# Arm_Board_2018.net
KiCad netlist of a schematic drawn in EAGLE
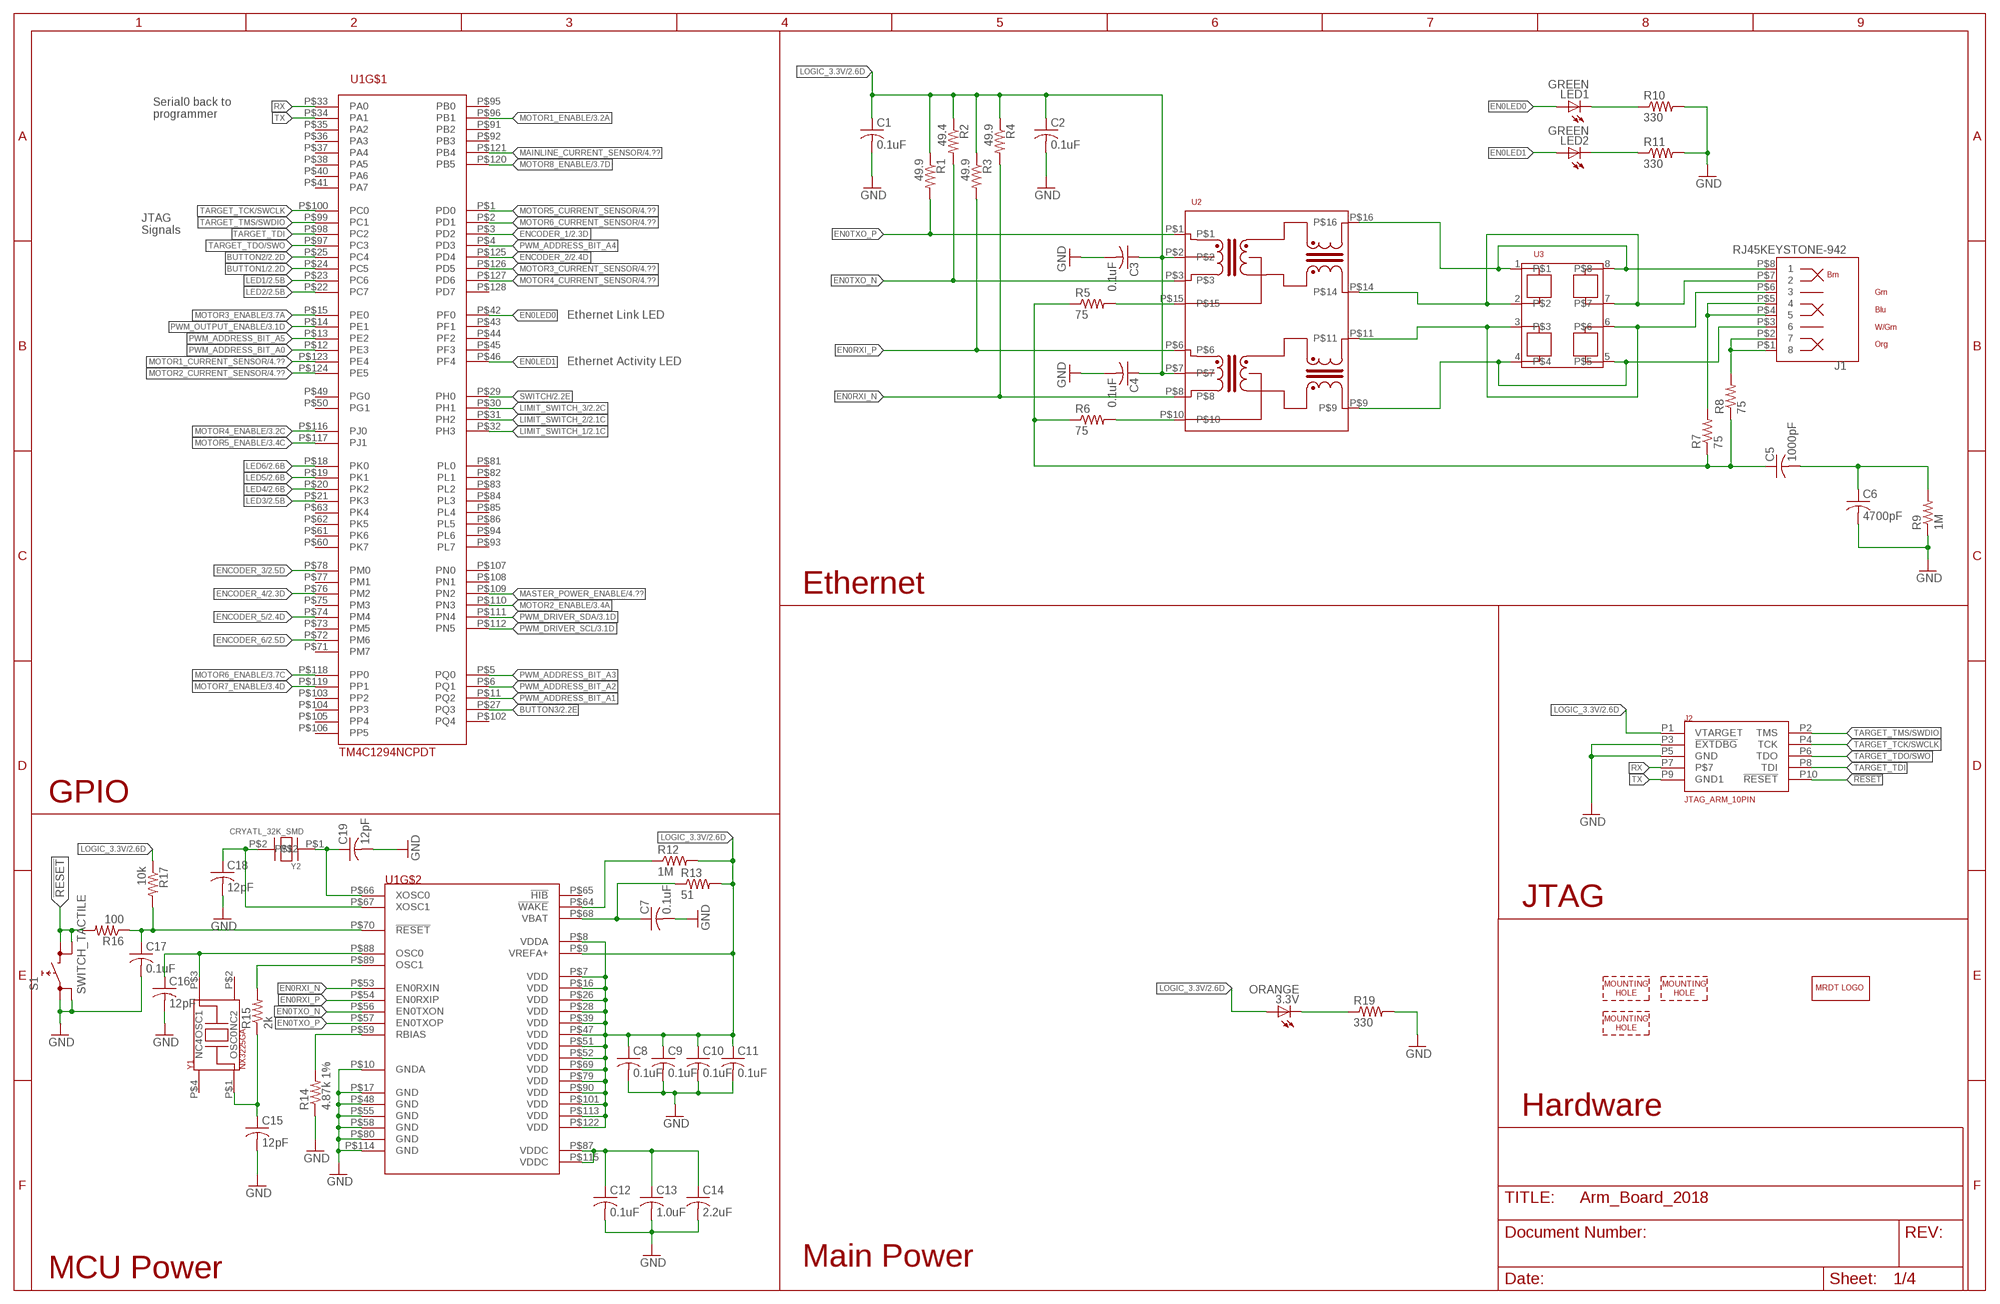
[diagram p0: schematic, sheet 1]
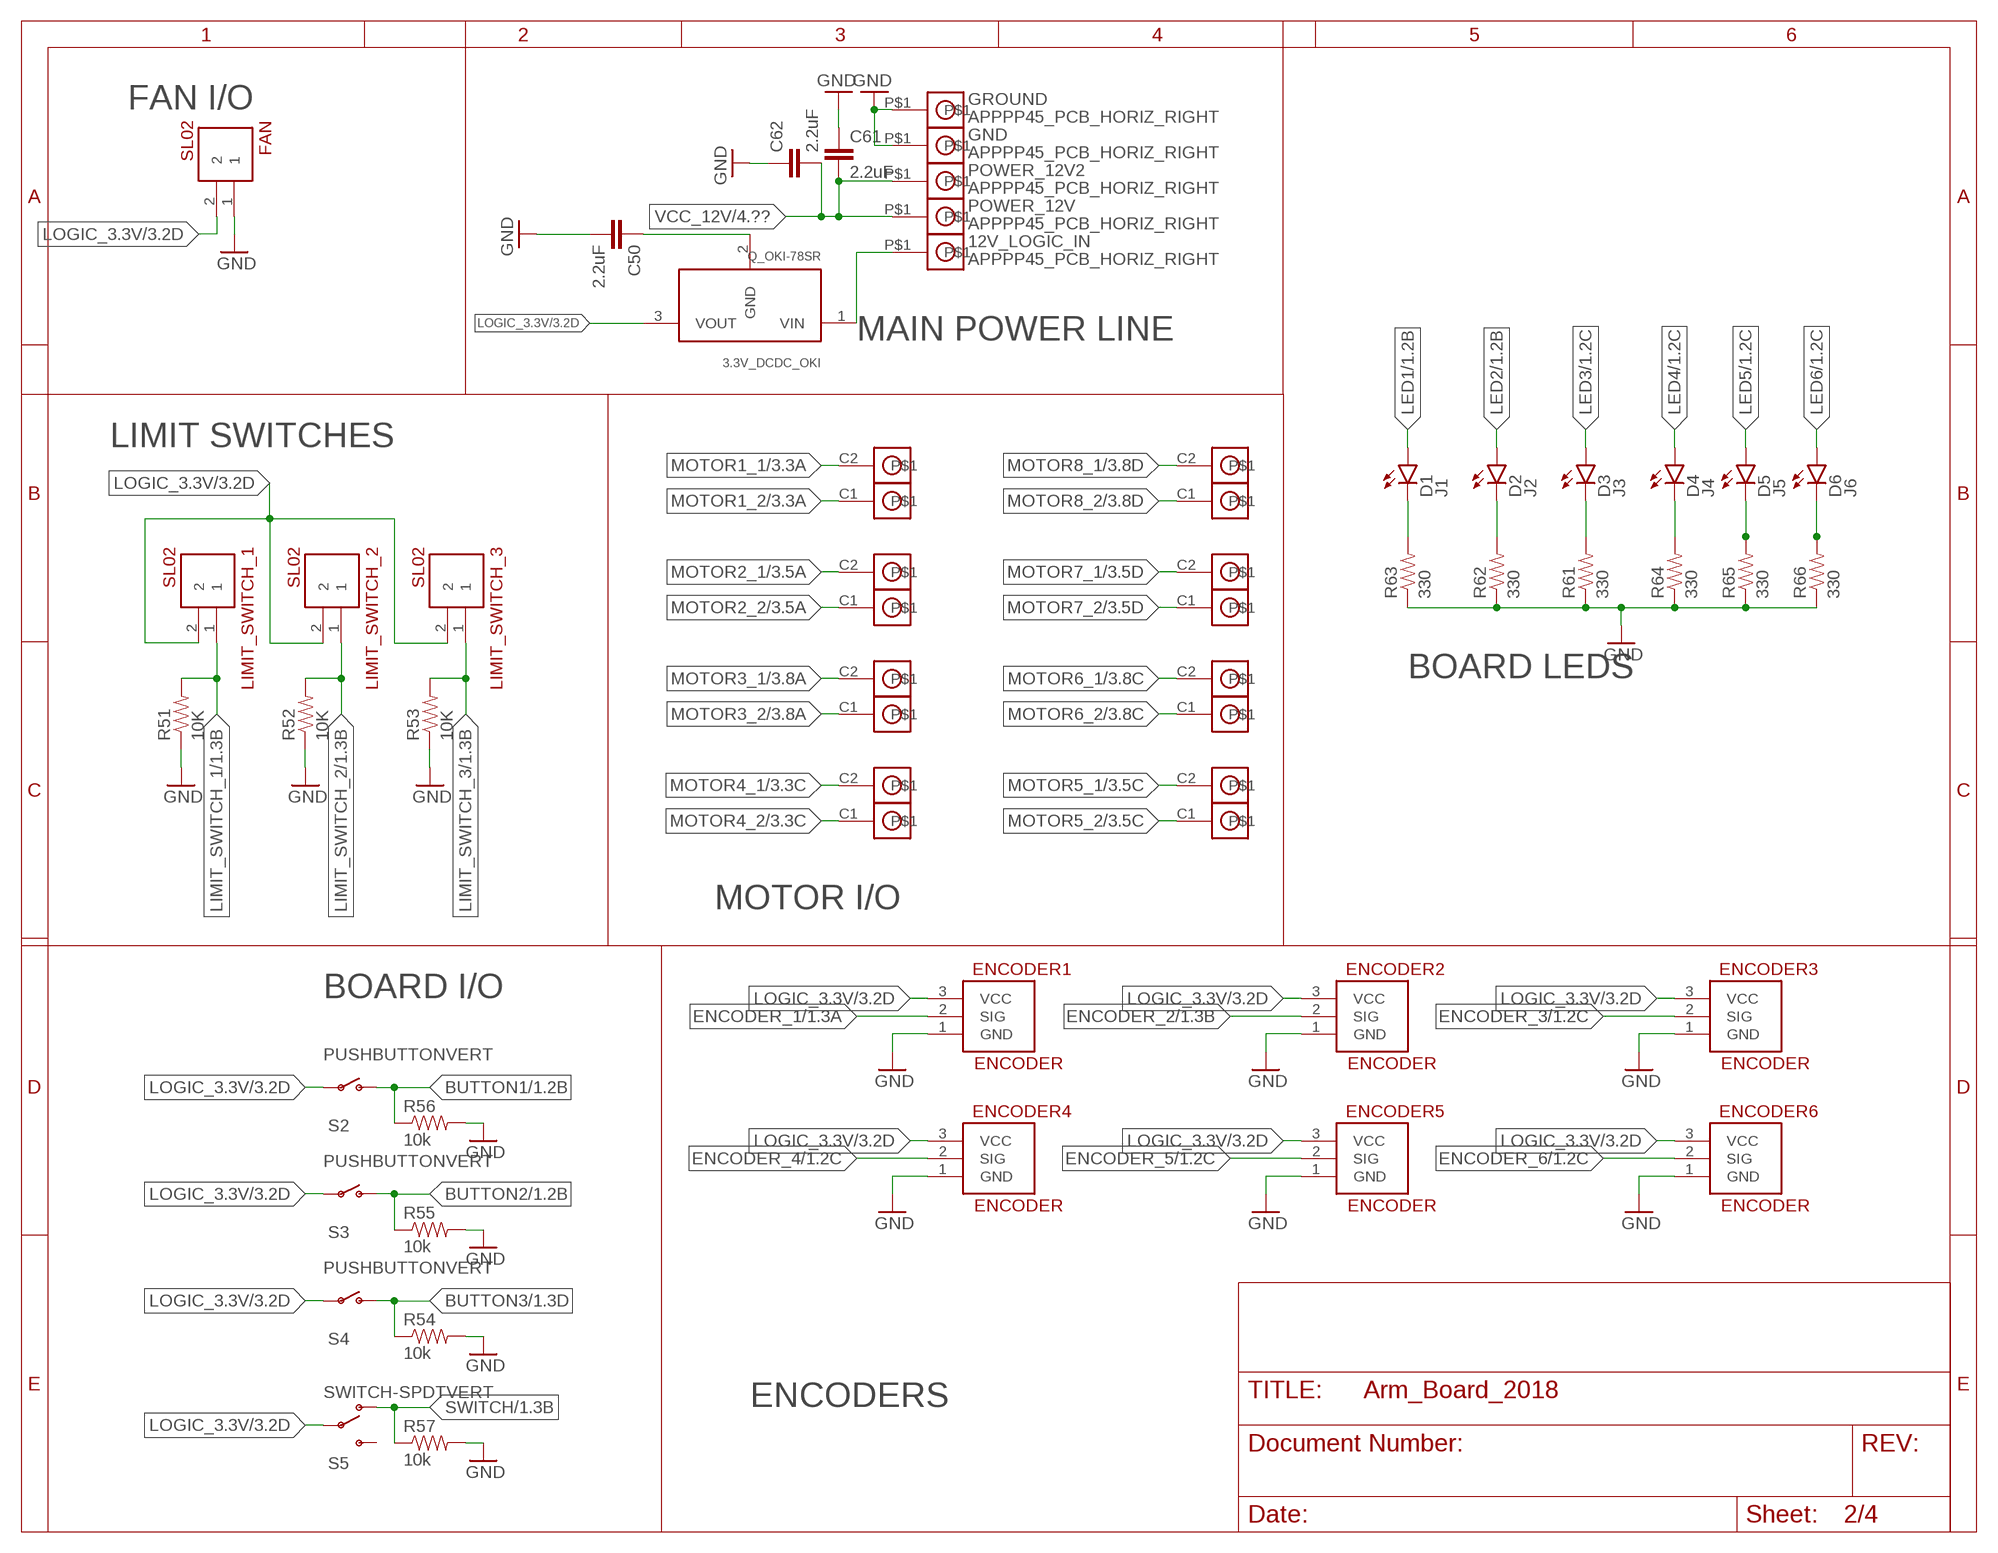
[diagram p1: schematic, sheet 2]
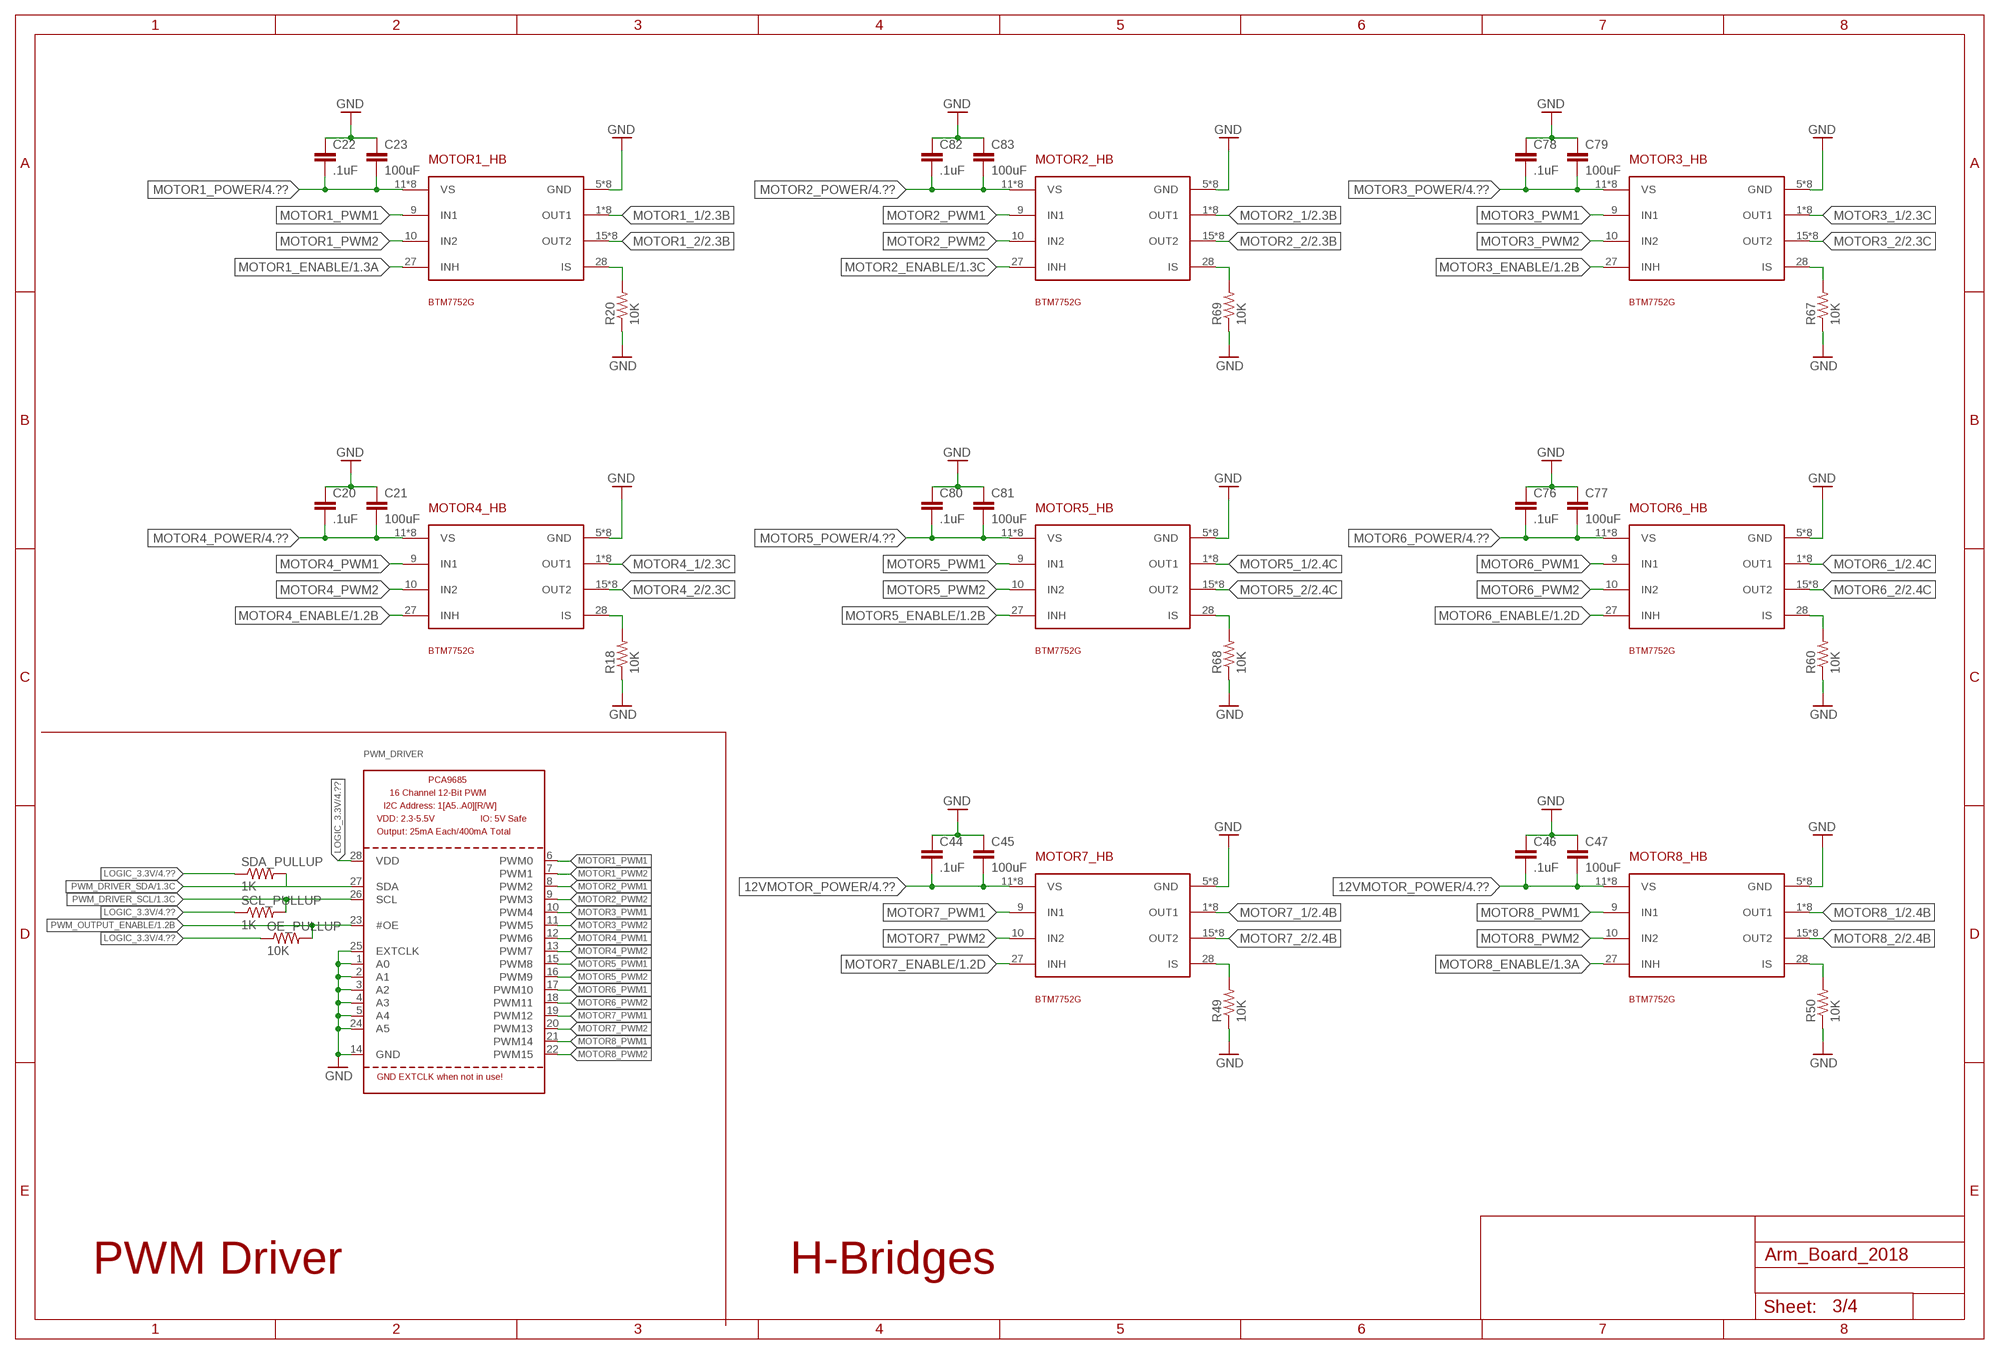
[diagram p2: schematic, sheet 3]
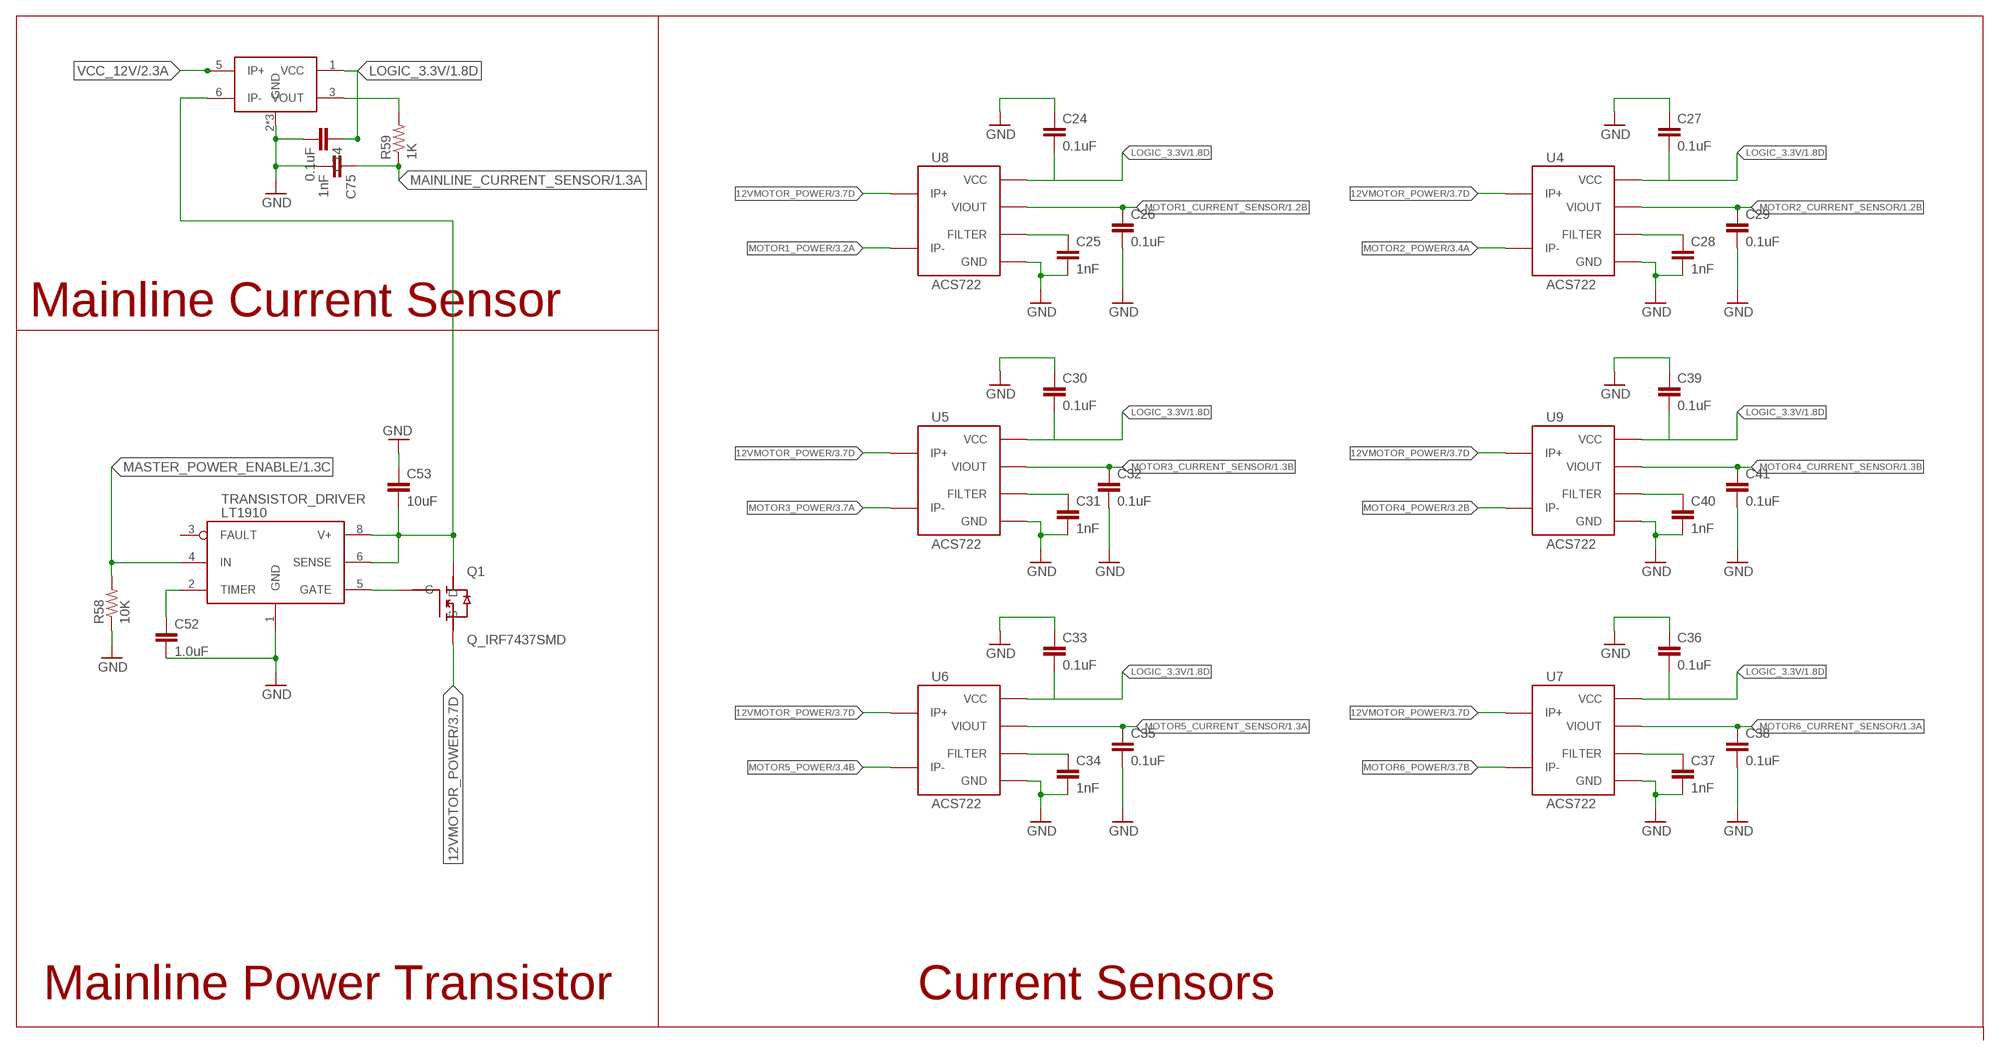
[diagram p3: schematic, sheet 4]

(export (version "E")
  (design (tool "Eeschema 10.0.6"))
  (components
    (comp (ref "3.3V")
      (value "ORANGE")
      (footprint "eagle-import:CHIP-LED0603")
      (libsource (lib "eagle-import") (part "LEDCHIP-LED0603"))
    )
    (comp (ref "C1")
      (value "0.1uF")
      (footprint "eagle-import:C0603")
      (libsource (lib "eagle-import") (part "C-USC0603"))
    )
    (comp (ref "C2")
      (value "0.1uF")
      (footprint "eagle-import:C0603")
      (libsource (lib "eagle-import") (part "C-USC0603"))
    )
    (comp (ref "C3")
      (value "0.1uF")
      (footprint "eagle-import:C0603")
      (libsource (lib "eagle-import") (part "C-USC0603"))
    )
    (comp (ref "C4")
      (value "0.1uF")
      (footprint "eagle-import:C0603")
      (libsource (lib "eagle-import") (part "C-USC0603"))
    )
    (comp (ref "C5")
      (value "1000pF")
      (footprint "eagle-import:C0603")
      (libsource (lib "eagle-import") (part "C-USC0603"))
    )
    (comp (ref "C6")
      (value "4700pF")
      (footprint "eagle-import:C1206")
      (libsource (lib "eagle-import") (part "C-USC1206"))
    )
    (comp (ref "C7")
      (value "0.1uF")
      (footprint "eagle-import:C0603")
      (libsource (lib "eagle-import") (part "C-USC0603"))
    )
    (comp (ref "C8")
      (value "0.1uF")
      (footprint "eagle-import:C0603")
      (libsource (lib "eagle-import") (part "C-USC0603"))
    )
    (comp (ref "C9")
      (value "0.1uF")
      (footprint "eagle-import:C0603")
      (libsource (lib "eagle-import") (part "C-USC0603"))
    )
    (comp (ref "C10")
      (value "0.1uF")
      (footprint "eagle-import:C0603")
      (libsource (lib "eagle-import") (part "C-USC0603"))
    )
    (comp (ref "C11")
      (value "0.1uF")
      (footprint "eagle-import:C0603")
      (libsource (lib "eagle-import") (part "C-USC0603"))
    )
    (comp (ref "C12")
      (value "0.1uF")
      (footprint "eagle-import:C0603")
      (libsource (lib "eagle-import") (part "C-USC0603"))
    )
    (comp (ref "C13")
      (value "1.0uF")
      (footprint "eagle-import:C0603")
      (libsource (lib "eagle-import") (part "C-USC0603"))
    )
    (comp (ref "C14")
      (value "2.2uF")
      (footprint "eagle-import:C0603")
      (libsource (lib "eagle-import") (part "C-USC0603"))
    )
    (comp (ref "C15")
      (value "12pF")
      (footprint "eagle-import:C0603")
      (libsource (lib "eagle-import") (part "C-USC0603"))
    )
    (comp (ref "C16")
      (value "12pF")
      (footprint "eagle-import:C0603")
      (libsource (lib "eagle-import") (part "C-USC0603"))
    )
    (comp (ref "C17")
      (value "0.1uF")
      (footprint "eagle-import:C0603")
      (libsource (lib "eagle-import") (part "C-USC0603"))
    )
    (comp (ref "C18")
      (value "12pF")
      (footprint "eagle-import:C0603")
      (libsource (lib "eagle-import") (part "C-USC0603"))
    )
    (comp (ref "C19")
      (value "12pF")
      (footprint "eagle-import:C0603")
      (libsource (lib "eagle-import") (part "C-USC0603"))
    )
    (comp (ref "J1")
      (value "RJ45KEYSTONE-942")
      (footprint "eagle-import:KEYSTONE-942")
      (libsource (lib "eagle-import") (part "RJ45KEYSTONE-942"))
    )
    (comp (ref "J2")
      (value "JTAG_ARM_10PIN")
      (footprint "eagle-import:CON_2X5_50MIL")
      (fields (field (name "PARTNO") "M50-3600542 "))
      (libsource (lib "eagle-import") (part "JTAG_ARM_10PIN"))
    )
    (comp (ref "LED1")
      (value "GREEN")
      (footprint "eagle-import:CHIP-LED0603")
      (libsource (lib "eagle-import") (part "LEDCHIP-LED0603"))
    )
    (comp (ref "LED2")
      (value "GREEN")
      (footprint "eagle-import:CHIP-LED0603")
      (libsource (lib "eagle-import") (part "LEDCHIP-LED0603"))
    )
    (comp (ref "R1")
      (value "49.9")
      (footprint "eagle-import:R0603")
      (libsource (lib "eagle-import") (part "R-US_R0603"))
    )
    (comp (ref "R2")
      (value "49.4")
      (footprint "eagle-import:R0603")
      (libsource (lib "eagle-import") (part "resistor_R-US_R0603"))
    )
    (comp (ref "R3")
      (value "49.9")
      (footprint "eagle-import:R0603")
      (libsource (lib "eagle-import") (part "resistor_R-US_R0603"))
    )
    (comp (ref "R4")
      (value "49.9")
      (footprint "eagle-import:R0603")
      (libsource (lib "eagle-import") (part "resistor_R-US_R0603"))
    )
    (comp (ref "R5")
      (value "75")
      (footprint "eagle-import:R0603")
      (libsource (lib "eagle-import") (part "resistor_R-US_R0603"))
    )
    (comp (ref "R6")
      (value "75")
      (footprint "eagle-import:R0603")
      (libsource (lib "eagle-import") (part "resistor_R-US_R0603"))
    )
    (comp (ref "R7")
      (value "75")
      (footprint "eagle-import:R0603")
      (libsource (lib "eagle-import") (part "resistor_R-US_R0603"))
    )
    (comp (ref "R8")
      (value "75")
      (footprint "eagle-import:R0603")
      (libsource (lib "eagle-import") (part "resistor_R-US_R0603"))
    )
    (comp (ref "R9")
      (value "1M")
      (footprint "eagle-import:R1206")
      (libsource (lib "eagle-import") (part "resistor_R-US_R1206"))
    )
    (comp (ref "R10")
      (value "330")
      (footprint "eagle-import:R0603")
      (libsource (lib "eagle-import") (part "resistor_R-US_R0603"))
    )
    (comp (ref "R11")
      (value "330")
      (footprint "eagle-import:R0603")
      (libsource (lib "eagle-import") (part "resistor_R-US_R0603"))
    )
    (comp (ref "R12")
      (value "1M")
      (footprint "eagle-import:R0603")
      (libsource (lib "eagle-import") (part "resistor_R-US_R0603"))
    )
    (comp (ref "R13")
      (value "51")
      (footprint "eagle-import:R0603")
      (libsource (lib "eagle-import") (part "resistor_R-US_R0603"))
    )
    (comp (ref "R14")
      (value "4.87k 1%")
      (footprint "eagle-import:R0603")
      (libsource (lib "eagle-import") (part "resistor_R-US_R0603"))
    )
    (comp (ref "R15")
      (value "2k")
      (footprint "eagle-import:R0603")
      (libsource (lib "eagle-import") (part "resistor_R-US_R0603"))
    )
    (comp (ref "R16")
      (value "100")
      (footprint "eagle-import:R0603")
      (libsource (lib "eagle-import") (part "resistor_R-US_R0603"))
    )
    (comp (ref "R17")
      (value "10k")
      (footprint "eagle-import:R0603")
      (libsource (lib "eagle-import") (part "resistor_R-US_R0603"))
    )
    (comp (ref "R19")
      (value "330")
      (footprint "eagle-import:R0603")
      (libsource (lib "eagle-import") (part "resistor_R-US_R0603"))
    )
    (comp (ref "S1")
      (value "SWITCH_TACTILE")
      (footprint "eagle-import:SWITCH_6MM_6MM_TE_CON_SMD")
      (libsource (lib "eagle-import") (part "SWITCH_TACTILE"))
    )
    (comp (ref "U$1")
      (value "MRDT_LOGO")
      (footprint "eagle-import:MRDT_LOGO")
      (libsource (lib "eagle-import") (part "MRDT_LOGO"))
    )
    (comp (ref "U$2")
      (value "MOUNTING_HOLE#6")
      (footprint "eagle-import:#6_SCREW")
      (libsource (lib "eagle-import") (part "MOUNTING_HOLE#6"))
    )
    (comp (ref "U$3")
      (value "MOUNTING_HOLE#6")
      (footprint "eagle-import:#6_SCREW")
      (libsource (lib "eagle-import") (part "MOUNTING_HOLE#6"))
    )
    (comp (ref "U$4")
      (value "MOUNTING_HOLE#6")
      (footprint "eagle-import:#6_SCREW")
      (libsource (lib "eagle-import") (part "MOUNTING_HOLE#6"))
    )
    (comp (ref "U1")
      (value "TM4C1294NCPDT")
      (footprint "eagle-import:TQFP-128")
      (libsource (lib "eagle-import") (part "TM4C1294NCPDT"))
    )
    (comp (ref "U2")
      (value "HX1198FNL")
      (footprint "eagle-import:HX1198FNL")
      (libsource (lib "eagle-import") (part "HX1198FNL"))
    )
    (comp (ref "U3")
      (value "SLVU2.8-4")
      (footprint "eagle-import:SOIC8")
      (libsource (lib "eagle-import") (part "SLVU2.8-4"))
    )
    (comp (ref "Y1")
      (value "NX3225GA")
      (footprint "eagle-import:NDK3.2X2.5")
      (libsource (lib "eagle-import") (part "NX3225GA"))
    )
    (comp (ref "Y2")
      (value "CRYATL_32K_SMD")
      (footprint "eagle-import:CRYSTAL_32K_SMD")
      (libsource (lib "eagle-import") (part "CRYATL_32K_SMD"))
    )
    (comp (ref "C20")
      (value ".1uF")
      (footprint "eagle-import:0603-CAP")
      (libsource (lib "eagle-import") (part "CAP0603-CAP"))
    )
    (comp (ref "C21")
      (value "100uF")
      (footprint "eagle-import:1210")
      (libsource (lib "eagle-import") (part "CAP1210"))
    )
    (comp (ref "C22")
      (value ".1uF")
      (footprint "eagle-import:0603-CAP")
      (libsource (lib "eagle-import") (part "CAP0603-CAP"))
    )
    (comp (ref "C23")
      (value "100uF")
      (footprint "eagle-import:1210")
      (libsource (lib "eagle-import") (part "CAP1210"))
    )
    (comp (ref "C44")
      (value ".1uF")
      (footprint "eagle-import:0603-CAP")
      (libsource (lib "eagle-import") (part "CAP0603-CAP"))
    )
    (comp (ref "C45")
      (value "100uF")
      (footprint "eagle-import:1210")
      (libsource (lib "eagle-import") (part "CAP1210"))
    )
    (comp (ref "C46")
      (value ".1uF")
      (footprint "eagle-import:0603-CAP")
      (libsource (lib "eagle-import") (part "CAP0603-CAP"))
    )
    (comp (ref "C47")
      (value "100uF")
      (footprint "eagle-import:1210")
      (libsource (lib "eagle-import") (part "CAP1210"))
    )
    (comp (ref "C76")
      (value ".1uF")
      (footprint "eagle-import:0603-CAP")
      (libsource (lib "eagle-import") (part "CAP0603-CAP"))
    )
    (comp (ref "C77")
      (value "100uF")
      (footprint "eagle-import:1210")
      (libsource (lib "eagle-import") (part "CAP1210"))
    )
    (comp (ref "C78")
      (value ".1uF")
      (footprint "eagle-import:0603-CAP")
      (libsource (lib "eagle-import") (part "CAP0603-CAP"))
    )
    (comp (ref "C79")
      (value "100uF")
      (footprint "eagle-import:1210")
      (libsource (lib "eagle-import") (part "CAP1210"))
    )
    (comp (ref "C80")
      (value ".1uF")
      (footprint "eagle-import:0603-CAP")
      (libsource (lib "eagle-import") (part "CAP0603-CAP"))
    )
    (comp (ref "C81")
      (value "100uF")
      (footprint "eagle-import:1210")
      (libsource (lib "eagle-import") (part "CAP1210"))
    )
    (comp (ref "C82")
      (value ".1uF")
      (footprint "eagle-import:0603-CAP")
      (libsource (lib "eagle-import") (part "CAP0603-CAP"))
    )
    (comp (ref "C83")
      (value "100uF")
      (footprint "eagle-import:1210")
      (libsource (lib "eagle-import") (part "CAP1210"))
    )
    (comp (ref "MOTOR1_HB")
      (value "BTM7752G")
      (footprint "eagle-import:36-BSSOP")
      (libsource (lib "eagle-import") (part "BTM7752G"))
    )
    (comp (ref "MOTOR2_HB")
      (value "BTM7752G")
      (footprint "eagle-import:36-BSSOP")
      (libsource (lib "eagle-import") (part "BTM7752G"))
    )
    (comp (ref "MOTOR3_HB")
      (value "BTM7752G")
      (footprint "eagle-import:36-BSSOP")
      (libsource (lib "eagle-import") (part "BTM7752G"))
    )
    (comp (ref "MOTOR4_HB")
      (value "BTM7752G")
      (footprint "eagle-import:36-BSSOP")
      (libsource (lib "eagle-import") (part "BTM7752G"))
    )
    (comp (ref "MOTOR5_HB")
      (value "BTM7752G")
      (footprint "eagle-import:36-BSSOP")
      (libsource (lib "eagle-import") (part "BTM7752G"))
    )
    (comp (ref "MOTOR6_HB")
      (value "BTM7752G")
      (footprint "eagle-import:36-BSSOP")
      (libsource (lib "eagle-import") (part "BTM7752G"))
    )
    (comp (ref "MOTOR7_HB")
      (value "BTM7752G")
      (footprint "eagle-import:36-BSSOP")
      (libsource (lib "eagle-import") (part "BTM7752G"))
    )
    (comp (ref "MOTOR8_HB")
      (value "BTM7752G")
      (footprint "eagle-import:36-BSSOP")
      (libsource (lib "eagle-import") (part "BTM7752G"))
    )
    (comp (ref "OE_PULLUP")
      (value "10K")
      (footprint "eagle-import:0402-RES")
      (libsource (lib "eagle-import") (part "RESISTOR0402-RES"))
    )
    (comp (ref "PWM_DRIVER")
      (value "PCA9685")
      (footprint "eagle-import:TSSOP28")
      (libsource (lib "eagle-import") (part "PCA9685"))
    )
    (comp (ref "R18")
      (value "10K")
      (footprint "eagle-import:0402-RES")
      (libsource (lib "eagle-import") (part "RESISTOR0402-RES"))
    )
    (comp (ref "R20")
      (value "10K")
      (footprint "eagle-import:0402-RES")
      (libsource (lib "eagle-import") (part "RESISTOR0402-RES"))
    )
    (comp (ref "R49")
      (value "10K")
      (footprint "eagle-import:0402-RES")
      (libsource (lib "eagle-import") (part "RESISTOR0402-RES"))
    )
    (comp (ref "R50")
      (value "10K")
      (footprint "eagle-import:0402-RES")
      (libsource (lib "eagle-import") (part "RESISTOR0402-RES"))
    )
    (comp (ref "R60")
      (value "10K")
      (footprint "eagle-import:0402-RES")
      (libsource (lib "eagle-import") (part "RESISTOR0402-RES"))
    )
    (comp (ref "R67")
      (value "10K")
      (footprint "eagle-import:0402-RES")
      (libsource (lib "eagle-import") (part "RESISTOR0402-RES"))
    )
    (comp (ref "R68")
      (value "10K")
      (footprint "eagle-import:0402-RES")
      (libsource (lib "eagle-import") (part "RESISTOR0402-RES"))
    )
    (comp (ref "R69")
      (value "10K")
      (footprint "eagle-import:0402-RES")
      (libsource (lib "eagle-import") (part "RESISTOR0402-RES"))
    )
    (comp (ref "SCL_PULLUP")
      (value "1K")
      (footprint "eagle-import:0402-RES")
      (libsource (lib "eagle-import") (part "RESISTOR0402-RES"))
    )
    (comp (ref "SDA_PULLUP")
      (value "1K")
      (footprint "eagle-import:0402-RES")
      (libsource (lib "eagle-import") (part "RESISTOR0402-RES"))
    )
    (comp (ref "3.3V_DCDC_OKI")
      (value "Q_OKI-78SR")
      (footprint "eagle-import:Q_OKI-78SR")
      (libsource (lib "eagle-import") (part "Q_OKI-78SR"))
    )
    (comp (ref "12V_LOGIC_IN")
      (value "APPPP45_PCB_HORIZ_RIGHT")
      (footprint "eagle-import:APP45_PCB_HORIZ_RIGHT")
      (libsource (lib "eagle-import") (part "APPPP45_PCB_HORIZ_RIGHT"))
    )
    (comp (ref "C50")
      (value "2.2uF")
      (footprint "eagle-import:0603-CAP")
      (libsource (lib "eagle-import") (part "CAP0603-CAP"))
    )
    (comp (ref "C61")
      (value "2.2uF")
      (footprint "eagle-import:1206")
      (libsource (lib "eagle-import") (part "CAP1206"))
    )
    (comp (ref "C62")
      (value "2.2uF")
      (footprint "eagle-import:1206")
      (libsource (lib "eagle-import") (part "CAP1206"))
    )
    (comp (ref "D1")
      (value "J1")
      (footprint "eagle-import:LED-0603")
      (libsource (lib "eagle-import") (part "LED0603"))
    )
    (comp (ref "D2")
      (value "J2")
      (footprint "eagle-import:LED-0603")
      (libsource (lib "eagle-import") (part "LED0603"))
    )
    (comp (ref "D3")
      (value "J3")
      (footprint "eagle-import:LED-0603")
      (libsource (lib "eagle-import") (part "LED0603"))
    )
    (comp (ref "D4")
      (value "J4")
      (footprint "eagle-import:LED-0603")
      (libsource (lib "eagle-import") (part "LED0603"))
    )
    (comp (ref "D5")
      (value "J5")
      (footprint "eagle-import:LED-0603")
      (libsource (lib "eagle-import") (part "LED0603"))
    )
    (comp (ref "D6")
      (value "J6")
      (footprint "eagle-import:LED-0603")
      (libsource (lib "eagle-import") (part "LED0603"))
    )
    (comp (ref "ENCODER1")
      (value "ENCODER")
      (footprint "eagle-import:MOLEX-70543-0002")
      (libsource (lib "eagle-import") (part "ENCODER"))
    )
    (comp (ref "ENCODER2")
      (value "ENCODER")
      (footprint "eagle-import:MOLEX-70543-0002")
      (libsource (lib "eagle-import") (part "ENCODER"))
    )
    (comp (ref "ENCODER3")
      (value "ENCODER")
      (footprint "eagle-import:MOLEX-70543-0002")
      (libsource (lib "eagle-import") (part "ENCODER"))
    )
    (comp (ref "ENCODER4")
      (value "ENCODER")
      (footprint "eagle-import:MOLEX-70543-0002")
      (libsource (lib "eagle-import") (part "ENCODER"))
    )
    (comp (ref "ENCODER5")
      (value "ENCODER")
      (footprint "eagle-import:MOLEX-70543-0002")
      (libsource (lib "eagle-import") (part "ENCODER"))
    )
    (comp (ref "ENCODER6")
      (value "ENCODER")
      (footprint "eagle-import:MOLEX-70543-0002")
      (libsource (lib "eagle-import") (part "ENCODER"))
    )
    (comp (ref "FAN")
      (value "SL02")
      (footprint "eagle-import:MOLEX-70543-0001")
      (libsource (lib "eagle-import") (part "SL02"))
    )
    (comp (ref "GND")
      (value "APPPP45_PCB_HORIZ_RIGHT")
      (footprint "eagle-import:APP45_PCB_HORIZ_RIGHT")
      (libsource (lib "eagle-import") (part "APPPP45_PCB_HORIZ_RIGHT"))
    )
    (comp (ref "GROUND")
      (value "APPPP45_PCB_HORIZ_RIGHT")
      (footprint "eagle-import:APP45_PCB_HORIZ_RIGHT")
      (libsource (lib "eagle-import") (part "APPPP45_PCB_HORIZ_RIGHT"))
    )
    (comp (ref "LIMIT_SWITCH_1")
      (value "SL02")
      (footprint "eagle-import:MOLEX-70543-0001")
      (libsource (lib "eagle-import") (part "SL02"))
    )
    (comp (ref "LIMIT_SWITCH_2")
      (value "SL02")
      (footprint "eagle-import:MOLEX-70543-0001")
      (libsource (lib "eagle-import") (part "SL02"))
    )
    (comp (ref "LIMIT_SWITCH_3")
      (value "SL02")
      (footprint "eagle-import:MOLEX-70543-0001")
      (libsource (lib "eagle-import") (part "SL02"))
    )
    (comp (ref "MOTOR1")
      (value "APP_2POS_CONFIGGENERAL_CONFIG")
      (footprint "eagle-import:APP45_HORIZ_CONFIG")
      (libsource (lib "eagle-import") (part "APP_2POS_CONFIGGENERAL_CONFIG"))
    )
    (comp (ref "MOTOR2")
      (value "APP_2POS_CONFIGGENERAL_CONFIG")
      (footprint "eagle-import:APP45_HORIZ_CONFIG")
      (libsource (lib "eagle-import") (part "APP_2POS_CONFIGGENERAL_CONFIG"))
    )
    (comp (ref "MOTOR3")
      (value "APP_2POS_CONFIGGENERAL_CONFIG")
      (footprint "eagle-import:APP45_HORIZ_CONFIG")
      (libsource (lib "eagle-import") (part "APP_2POS_CONFIGGENERAL_CONFIG"))
    )
    (comp (ref "MOTOR4")
      (value "APP_2POS_CONFIGGENERAL_CONFIG")
      (footprint "eagle-import:APP45_HORIZ_CONFIG")
      (libsource (lib "eagle-import") (part "APP_2POS_CONFIGGENERAL_CONFIG"))
    )
    (comp (ref "MOTOR5")
      (value "APP_2POS_CONFIGGENERAL_CONFIG")
      (footprint "eagle-import:APP45_HORIZ_CONFIG")
      (libsource (lib "eagle-import") (part "APP_2POS_CONFIGGENERAL_CONFIG"))
    )
    (comp (ref "MOTOR6")
      (value "APP_2POS_CONFIGGENERAL_CONFIG")
      (footprint "eagle-import:APP45_HORIZ_CONFIG")
      (libsource (lib "eagle-import") (part "APP_2POS_CONFIGGENERAL_CONFIG"))
    )
    (comp (ref "MOTOR7")
      (value "APP_2POS_CONFIGGENERAL_CONFIG")
      (footprint "eagle-import:APP45_HORIZ_CONFIG")
      (libsource (lib "eagle-import") (part "APP_2POS_CONFIGGENERAL_CONFIG"))
    )
    (comp (ref "MOTOR8")
      (value "APP_2POS_CONFIGGENERAL_CONFIG")
      (footprint "eagle-import:APP45_HORIZ_CONFIG")
      (libsource (lib "eagle-import") (part "APP_2POS_CONFIGGENERAL_CONFIG"))
    )
    (comp (ref "POWER_12V")
      (value "APPPP45_PCB_HORIZ_RIGHT")
      (footprint "eagle-import:APP45_PCB_HORIZ_RIGHT")
      (libsource (lib "eagle-import") (part "APPPP45_PCB_HORIZ_RIGHT"))
    )
    (comp (ref "POWER_12V2")
      (value "APPPP45_PCB_HORIZ_RIGHT")
      (footprint "eagle-import:APP45_PCB_HORIZ_RIGHT")
      (libsource (lib "eagle-import") (part "APPPP45_PCB_HORIZ_RIGHT"))
    )
    (comp (ref "R51")
      (value "10K")
      (footprint "eagle-import:0402-RES")
      (libsource (lib "eagle-import") (part "RESISTOR0402-RES"))
    )
    (comp (ref "R52")
      (value "10K")
      (footprint "eagle-import:0402-RES")
      (libsource (lib "eagle-import") (part "RESISTOR0402-RES"))
    )
    (comp (ref "R53")
      (value "10K")
      (footprint "eagle-import:0402-RES")
      (libsource (lib "eagle-import") (part "RESISTOR0402-RES"))
    )
    (comp (ref "R54")
      (value "10k")
      (footprint "eagle-import:0402-RES")
      (libsource (lib "eagle-import") (part "RESISTOR0402-RES"))
    )
    (comp (ref "R55")
      (value "10k")
      (footprint "eagle-import:0402-RES")
      (libsource (lib "eagle-import") (part "RESISTOR0402-RES"))
    )
    (comp (ref "R56")
      (value "10k")
      (footprint "eagle-import:0402-RES")
      (libsource (lib "eagle-import") (part "RESISTOR0402-RES"))
    )
    (comp (ref "R57")
      (value "10k")
      (footprint "eagle-import:0402-RES")
      (libsource (lib "eagle-import") (part "RESISTOR0402-RES"))
    )
    (comp (ref "R61")
      (value "330")
      (footprint "eagle-import:0402-RES")
      (libsource (lib "eagle-import") (part "RESISTOR0402-RES"))
    )
    (comp (ref "R62")
      (value "330")
      (footprint "eagle-import:0402-RES")
      (libsource (lib "eagle-import") (part "RESISTOR0402-RES"))
    )
    (comp (ref "R63")
      (value "330")
      (footprint "eagle-import:0402-RES")
      (libsource (lib "eagle-import") (part "RESISTOR0402-RES"))
    )
    (comp (ref "R64")
      (value "330")
      (footprint "eagle-import:0402-RES")
      (libsource (lib "eagle-import") (part "RESISTOR0402-RES"))
    )
    (comp (ref "R65")
      (value "330")
      (footprint "eagle-import:0402-RES")
      (libsource (lib "eagle-import") (part "RESISTOR0402-RES"))
    )
    (comp (ref "R66")
      (value "330")
      (footprint "eagle-import:0402-RES")
      (libsource (lib "eagle-import") (part "RESISTOR0402-RES"))
    )
    (comp (ref "S2")
      (value "PUSHBUTTONVERT")
      (footprint "eagle-import:APEM-MJTP1243")
      (fields (field (name "PARTNO") "MJTP1243"))
      (libsource (lib "eagle-import") (part "PUSHBUTTONVERT"))
    )
    (comp (ref "S3")
      (value "PUSHBUTTONVERT")
      (footprint "eagle-import:APEM-MJTP1243")
      (fields (field (name "PARTNO") "MJTP1243"))
      (libsource (lib "eagle-import") (part "PUSHBUTTONVERT"))
    )
    (comp (ref "S4")
      (value "PUSHBUTTONVERT")
      (footprint "eagle-import:APEM-MJTP1243")
      (fields (field (name "PARTNO") "MJTP1243"))
      (libsource (lib "eagle-import") (part "PUSHBUTTONVERT"))
    )
    (comp (ref "S5")
      (value "SWITCH-SPDTVERT")
      (footprint "eagle-import:C&K-SS12D07VG4NSGAPA")
      (fields (field (name "PARTNO") "SS12D07VG4NSGAPA"))
      (libsource (lib "eagle-import") (part "SWITCH-SPDTVERT"))
    )
    (comp (ref "C24")
      (value "0.1uF")
      (footprint "eagle-import:0603-CAP")
      (libsource (lib "eagle-import") (part "CAP0603-CAP"))
    )
    (comp (ref "C25")
      (value "1nF")
      (footprint "eagle-import:0603-CAP")
      (libsource (lib "eagle-import") (part "CAP0603-CAP"))
    )
    (comp (ref "C26")
      (value "0.1uF")
      (footprint "eagle-import:0603-CAP")
      (libsource (lib "eagle-import") (part "CAP0603-CAP"))
    )
    (comp (ref "C27")
      (value "0.1uF")
      (footprint "eagle-import:0603-CAP")
      (libsource (lib "eagle-import") (part "CAP0603-CAP"))
    )
    (comp (ref "C28")
      (value "1nF")
      (footprint "eagle-import:0603-CAP")
      (libsource (lib "eagle-import") (part "CAP0603-CAP"))
    )
    (comp (ref "C29")
      (value "0.1uF")
      (footprint "eagle-import:0603-CAP")
      (libsource (lib "eagle-import") (part "CAP0603-CAP"))
    )
    (comp (ref "C30")
      (value "0.1uF")
      (footprint "eagle-import:0603-CAP")
      (libsource (lib "eagle-import") (part "CAP0603-CAP"))
    )
    (comp (ref "C31")
      (value "1nF")
      (footprint "eagle-import:0603-CAP")
      (libsource (lib "eagle-import") (part "CAP0603-CAP"))
    )
    (comp (ref "C32")
      (value "0.1uF")
      (footprint "eagle-import:0603-CAP")
      (libsource (lib "eagle-import") (part "CAP0603-CAP"))
    )
    (comp (ref "C33")
      (value "0.1uF")
      (footprint "eagle-import:0603-CAP")
      (libsource (lib "eagle-import") (part "CAP0603-CAP"))
    )
    (comp (ref "C34")
      (value "1nF")
      (footprint "eagle-import:0603-CAP")
      (libsource (lib "eagle-import") (part "CAP0603-CAP"))
    )
    (comp (ref "C35")
      (value "0.1uF")
      (footprint "eagle-import:0603-CAP")
      (libsource (lib "eagle-import") (part "CAP0603-CAP"))
    )
    (comp (ref "C36")
      (value "0.1uF")
      (footprint "eagle-import:0603-CAP")
      (libsource (lib "eagle-import") (part "CAP0603-CAP"))
    )
    (comp (ref "C37")
      (value "1nF")
      (footprint "eagle-import:0603-CAP")
      (libsource (lib "eagle-import") (part "CAP0603-CAP"))
    )
    (comp (ref "C38")
      (value "0.1uF")
      (footprint "eagle-import:0603-CAP")
      (libsource (lib "eagle-import") (part "CAP0603-CAP"))
    )
    (comp (ref "C39")
      (value "0.1uF")
      (footprint "eagle-import:0603-CAP")
      (libsource (lib "eagle-import") (part "CAP0603-CAP"))
    )
    (comp (ref "C40")
      (value "1nF")
      (footprint "eagle-import:0603-CAP")
      (libsource (lib "eagle-import") (part "CAP0603-CAP"))
    )
    (comp (ref "C41")
      (value "0.1uF")
      (footprint "eagle-import:0603-CAP")
      (libsource (lib "eagle-import") (part "CAP0603-CAP"))
    )
    (comp (ref "C52")
      (value "1.0uF")
      (footprint "eagle-import:0603-CAP")
      (libsource (lib "eagle-import") (part "CAP0603-CAP"))
    )
    (comp (ref "C53")
      (value "10uF")
      (footprint "eagle-import:0603-CAP")
      (libsource (lib "eagle-import") (part "CAP0603-CAP"))
    )
    (comp (ref "C74")
      (value "0.1uF")
      (footprint "eagle-import:0603-CAP")
      (libsource (lib "eagle-import") (part "CAP0603-CAP"))
    )
    (comp (ref "C75")
      (value "1nF")
      (footprint "eagle-import:0603-CAP")
      (libsource (lib "eagle-import") (part "CAP0603-CAP"))
    )
    (comp (ref "MAINLINE_CURRENT")
      (value "ACS781")
      (footprint "eagle-import:7-POWER_SMD_MODULE")
      (libsource (lib "eagle-import") (part "ACS781"))
    )
    (comp (ref "Q1")
      (value "Q_IRF7437SMD")
      (footprint "eagle-import:D2PACK")
      (libsource (lib "eagle-import") (part "Q_IRF7437SMD"))
    )
    (comp (ref "R58")
      (value "10K")
      (footprint "eagle-import:0402-RES")
      (libsource (lib "eagle-import") (part "RESISTOR0402-RES"))
    )
    (comp (ref "R59")
      (value "1K")
      (footprint "eagle-import:0402-RES")
      (libsource (lib "eagle-import") (part "RESISTOR0402-RES"))
    )
    (comp (ref "TRANSISTOR_DRIVER")
      (value "LT1910")
      (footprint "eagle-import:SO8")
      (libsource (lib "eagle-import") (part "LT1910"))
    )
    (comp (ref "U4")
      (value "ACS722")
      (footprint "eagle-import:SOIC8")
      (libsource (lib "eagle-import") (part "ACS722"))
    )
    (comp (ref "U5")
      (value "ACS722")
      (footprint "eagle-import:SOIC8")
      (libsource (lib "eagle-import") (part "ACS722"))
    )
    (comp (ref "U6")
      (value "ACS722")
      (footprint "eagle-import:SOIC8")
      (libsource (lib "eagle-import") (part "ACS722"))
    )
    (comp (ref "U7")
      (value "ACS722")
      (footprint "eagle-import:SOIC8")
      (libsource (lib "eagle-import") (part "ACS722"))
    )
    (comp (ref "U8")
      (value "ACS722")
      (footprint "eagle-import:SOIC8")
      (libsource (lib "eagle-import") (part "ACS722"))
    )
    (comp (ref "U9")
      (value "ACS722")
      (footprint "eagle-import:SOIC8")
      (libsource (lib "eagle-import") (part "ACS722"))
    )
  )
  (nets
    (net (code "1") (name "12VMOTOR_POWER") (class "Default")
      (node (ref "C44") (pin "2") (pinfunction "2_2") (pintype "passive"))
      (node (ref "C45") (pin "2") (pinfunction "2_2") (pintype "passive"))
      (node (ref "C46") (pin "2") (pinfunction "2_2") (pintype "passive"))
      (node (ref "C47") (pin "2") (pinfunction "2_2") (pintype "passive"))
      (node (ref "MOTOR7_HB") (pin "11") (pinfunction "VS_11") (pintype "bidirectional"))
      (node (ref "MOTOR7_HB") (pin "12") (pinfunction "VS_12") (pintype "bidirectional"))
      (node (ref "MOTOR7_HB") (pin "13") (pinfunction "VS_13") (pintype "bidirectional"))
      (node (ref "MOTOR7_HB") (pin "14") (pinfunction "VS_14") (pintype "bidirectional"))
      (node (ref "MOTOR7_HB") (pin "29") (pinfunction "VS_29") (pintype "bidirectional"))
      (node (ref "MOTOR7_HB") (pin "30") (pinfunction "VS_30") (pintype "bidirectional"))
      (node (ref "MOTOR7_HB") (pin "31") (pinfunction "VS_31") (pintype "bidirectional"))
      (node (ref "MOTOR7_HB") (pin "32") (pinfunction "VS_32") (pintype "bidirectional"))
      (node (ref "MOTOR8_HB") (pin "11") (pinfunction "VS_11") (pintype "bidirectional"))
      (node (ref "MOTOR8_HB") (pin "12") (pinfunction "VS_12") (pintype "bidirectional"))
      (node (ref "MOTOR8_HB") (pin "13") (pinfunction "VS_13") (pintype "bidirectional"))
      (node (ref "MOTOR8_HB") (pin "14") (pinfunction "VS_14") (pintype "bidirectional"))
      (node (ref "MOTOR8_HB") (pin "29") (pinfunction "VS_29") (pintype "bidirectional"))
      (node (ref "MOTOR8_HB") (pin "30") (pinfunction "VS_30") (pintype "bidirectional"))
      (node (ref "MOTOR8_HB") (pin "31") (pinfunction "VS_31") (pintype "bidirectional"))
      (node (ref "MOTOR8_HB") (pin "32") (pinfunction "VS_32") (pintype "bidirectional"))
      (node (ref "Q1") (pin "2") (pinfunction "S_2") (pintype "bidirectional"))
      (node (ref "U4") (pin "1") (pinfunction "IP+_1") (pintype "bidirectional"))
      (node (ref "U4") (pin "2") (pinfunction "IP+_2") (pintype "bidirectional"))
      (node (ref "U5") (pin "1") (pinfunction "IP+_1") (pintype "bidirectional"))
      (node (ref "U5") (pin "2") (pinfunction "IP+_2") (pintype "bidirectional"))
      (node (ref "U6") (pin "1") (pinfunction "IP+_1") (pintype "bidirectional"))
      (node (ref "U6") (pin "2") (pinfunction "IP+_2") (pintype "bidirectional"))
      (node (ref "U7") (pin "1") (pinfunction "IP+_1") (pintype "bidirectional"))
      (node (ref "U7") (pin "2") (pinfunction "IP+_2") (pintype "bidirectional"))
      (node (ref "U8") (pin "1") (pinfunction "IP+_1") (pintype "bidirectional"))
      (node (ref "U8") (pin "2") (pinfunction "IP+_2") (pintype "bidirectional"))
      (node (ref "U9") (pin "1") (pinfunction "IP+_1") (pintype "bidirectional"))
      (node (ref "U9") (pin "2") (pinfunction "IP+_2") (pintype "bidirectional"))
    )
    (net (code "2") (name "BUTTON1") (class "Default")
      (node (ref "R56") (pin "1") (pinfunction "1_1") (pintype "passive"))
      (node (ref "S2") (pin "P$2") (pinfunction "S_P$2") (pintype "passive"))
      (node (ref "U1") (pin "P$24") (pinfunction "PC5_P$24") (pintype "bidirectional"))
    )
    (net (code "3") (name "BUTTON2") (class "Default")
      (node (ref "R55") (pin "1") (pinfunction "1_1") (pintype "passive"))
      (node (ref "S3") (pin "P$2") (pinfunction "S_P$2") (pintype "passive"))
      (node (ref "U1") (pin "P$25") (pinfunction "PC4_P$25") (pintype "bidirectional"))
    )
    (net (code "4") (name "BUTTON3") (class "Default")
      (node (ref "R54") (pin "1") (pinfunction "1_1") (pintype "passive"))
      (node (ref "S4") (pin "P$2") (pinfunction "S_P$2") (pintype "passive"))
      (node (ref "U1") (pin "P$27") (pinfunction "PQ3_P$27") (pintype "bidirectional"))
    )
    (net (code "5") (name "EN0LED0") (class "Default")
      (node (ref "LED1") (pin "A") (pinfunction "A_A") (pintype "passive"))
      (node (ref "U1") (pin "P$42") (pinfunction "PF0_P$42") (pintype "bidirectional"))
    )
    (net (code "6") (name "EN0LED1") (class "Default")
      (node (ref "LED2") (pin "A") (pinfunction "A_A") (pintype "passive"))
      (node (ref "U1") (pin "P$46") (pinfunction "PF4_P$46") (pintype "bidirectional"))
    )
    (net (code "7") (name "EN0RXI_N") (class "Default")
      (node (ref "R4") (pin "2") (pinfunction "2_2") (pintype "passive"))
      (node (ref "U1") (pin "P$53") (pinfunction "EN0RXIN_P$53") (pintype "bidirectional"))
      (node (ref "U2") (pin "P$8") (pinfunction "P$8_P$8") (pintype "bidirectional"))
    )
    (net (code "8") (name "EN0RXI_P") (class "Default")
      (node (ref "R3") (pin "2") (pinfunction "2_2") (pintype "passive"))
      (node (ref "U1") (pin "P$54") (pinfunction "EN0RXIP_P$54") (pintype "bidirectional"))
      (node (ref "U2") (pin "P$6") (pinfunction "P$6_P$6") (pintype "bidirectional"))
    )
    (net (code "9") (name "EN0TXO_N") (class "Default")
      (node (ref "R2") (pin "2") (pinfunction "2_2") (pintype "passive"))
      (node (ref "U1") (pin "P$56") (pinfunction "EN0TXON_P$56") (pintype "bidirectional"))
      (node (ref "U2") (pin "P$3") (pinfunction "P$3_P$3") (pintype "bidirectional"))
    )
    (net (code "10") (name "EN0TXO_P") (class "Default")
      (node (ref "R1") (pin "2") (pinfunction "2_2") (pintype "passive"))
      (node (ref "U1") (pin "P$57") (pinfunction "EN0TXOP_P$57") (pintype "bidirectional"))
      (node (ref "U2") (pin "P$1") (pinfunction "P$1_P$1") (pintype "bidirectional"))
    )
    (net (code "11") (name "ENCODER_1") (class "Default")
      (node (ref "ENCODER1") (pin "2") (pinfunction "SIG_2") (pintype "bidirectional"))
      (node (ref "U1") (pin "P$3") (pinfunction "PD2_P$3") (pintype "bidirectional"))
    )
    (net (code "12") (name "ENCODER_2") (class "Default")
      (node (ref "ENCODER2") (pin "2") (pinfunction "SIG_2") (pintype "bidirectional"))
      (node (ref "U1") (pin "P$125") (pinfunction "PD4_P$125") (pintype "bidirectional"))
    )
    (net (code "13") (name "ENCODER_3") (class "Default")
      (node (ref "ENCODER3") (pin "2") (pinfunction "SIG_2") (pintype "bidirectional"))
      (node (ref "U1") (pin "P$78") (pinfunction "PM0_P$78") (pintype "bidirectional"))
    )
    (net (code "14") (name "ENCODER_4") (class "Default")
      (node (ref "ENCODER4") (pin "2") (pinfunction "SIG_2") (pintype "bidirectional"))
      (node (ref "U1") (pin "P$76") (pinfunction "PM2_P$76") (pintype "bidirectional"))
    )
    (net (code "15") (name "ENCODER_5") (class "Default")
      (node (ref "ENCODER5") (pin "2") (pinfunction "SIG_2") (pintype "bidirectional"))
      (node (ref "U1") (pin "P$74") (pinfunction "PM4_P$74") (pintype "bidirectional"))
    )
    (net (code "16") (name "ENCODER_6") (class "Default")
      (node (ref "ENCODER6") (pin "2") (pinfunction "SIG_2") (pintype "bidirectional"))
      (node (ref "U1") (pin "P$72") (pinfunction "PM6_P$72") (pintype "bidirectional"))
    )
    (net (code "17") (name "GND") (class "Default")
      (node (ref "C1") (pin "2") (pinfunction "2_2") (pintype "passive"))
      (node (ref "C10") (pin "2") (pinfunction "2_2") (pintype "passive"))
      (node (ref "C11") (pin "2") (pinfunction "2_2") (pintype "passive"))
      (node (ref "C12") (pin "2") (pinfunction "2_2") (pintype "passive"))
      (node (ref "C13") (pin "2") (pinfunction "2_2") (pintype "passive"))
      (node (ref "C14") (pin "2") (pinfunction "2_2") (pintype "passive"))
      (node (ref "C15") (pin "2") (pinfunction "2_2") (pintype "passive"))
      (node (ref "C16") (pin "2") (pinfunction "2_2") (pintype "passive"))
      (node (ref "C17") (pin "2") (pinfunction "2_2") (pintype "passive"))
      (node (ref "C18") (pin "2") (pinfunction "2_2") (pintype "passive"))
      (node (ref "C19") (pin "2") (pinfunction "2_2") (pintype "passive"))
      (node (ref "C2") (pin "2") (pinfunction "2_2") (pintype "passive"))
      (node (ref "C20") (pin "1") (pinfunction "1_1") (pintype "passive"))
      (node (ref "C21") (pin "1") (pinfunction "1_1") (pintype "passive"))
      (node (ref "C22") (pin "1") (pinfunction "1_1") (pintype "passive"))
      (node (ref "C23") (pin "1") (pinfunction "1_1") (pintype "passive"))
      (node (ref "C24") (pin "1") (pinfunction "1_1") (pintype "passive"))
      (node (ref "C25") (pin "2") (pinfunction "2_2") (pintype "passive"))
      (node (ref "C26") (pin "2") (pinfunction "2_2") (pintype "passive"))
      (node (ref "C27") (pin "1") (pinfunction "1_1") (pintype "passive"))
      (node (ref "C28") (pin "2") (pinfunction "2_2") (pintype "passive"))
      (node (ref "C29") (pin "2") (pinfunction "2_2") (pintype "passive"))
      (node (ref "C3") (pin "2") (pinfunction "2_2") (pintype "passive"))
      (node (ref "C30") (pin "1") (pinfunction "1_1") (pintype "passive"))
      (node (ref "C31") (pin "2") (pinfunction "2_2") (pintype "passive"))
      (node (ref "C32") (pin "2") (pinfunction "2_2") (pintype "passive"))
      (node (ref "C33") (pin "1") (pinfunction "1_1") (pintype "passive"))
      (node (ref "C34") (pin "2") (pinfunction "2_2") (pintype "passive"))
      (node (ref "C35") (pin "2") (pinfunction "2_2") (pintype "passive"))
      (node (ref "C36") (pin "1") (pinfunction "1_1") (pintype "passive"))
      (node (ref "C37") (pin "2") (pinfunction "2_2") (pintype "passive"))
      (node (ref "C38") (pin "2") (pinfunction "2_2") (pintype "passive"))
      (node (ref "C39") (pin "1") (pinfunction "1_1") (pintype "passive"))
      (node (ref "C4") (pin "2") (pinfunction "2_2") (pintype "passive"))
      (node (ref "C40") (pin "2") (pinfunction "2_2") (pintype "passive"))
      (node (ref "C41") (pin "2") (pinfunction "2_2") (pintype "passive"))
      (node (ref "C44") (pin "1") (pinfunction "1_1") (pintype "passive"))
      (node (ref "C45") (pin "1") (pinfunction "1_1") (pintype "passive"))
      (node (ref "C46") (pin "1") (pinfunction "1_1") (pintype "passive"))
      (node (ref "C47") (pin "1") (pinfunction "1_1") (pintype "passive"))
      (node (ref "C50") (pin "2") (pinfunction "2_2") (pintype "passive"))
      (node (ref "C52") (pin "2") (pinfunction "2_2") (pintype "passive"))
      (node (ref "C53") (pin "1") (pinfunction "1_1") (pintype "passive"))
      (node (ref "C6") (pin "2") (pinfunction "2_2") (pintype "passive"))
      (node (ref "C61") (pin "1") (pinfunction "1_1") (pintype "passive"))
      (node (ref "C62") (pin "1") (pinfunction "1_1") (pintype "passive"))
      (node (ref "C7") (pin "2") (pinfunction "2_2") (pintype "passive"))
      (node (ref "C74") (pin "2") (pinfunction "2_2") (pintype "passive"))
      (node (ref "C75") (pin "2") (pinfunction "2_2") (pintype "passive"))
      (node (ref "C76") (pin "1") (pinfunction "1_1") (pintype "passive"))
      (node (ref "C77") (pin "1") (pinfunction "1_1") (pintype "passive"))
      (node (ref "C78") (pin "1") (pinfunction "1_1") (pintype "passive"))
      (node (ref "C79") (pin "1") (pinfunction "1_1") (pintype "passive"))
      (node (ref "C8") (pin "2") (pinfunction "2_2") (pintype "passive"))
      (node (ref "C80") (pin "1") (pinfunction "1_1") (pintype "passive"))
      (node (ref "C81") (pin "1") (pinfunction "1_1") (pintype "passive"))
      (node (ref "C82") (pin "1") (pinfunction "1_1") (pintype "passive"))
      (node (ref "C83") (pin "1") (pinfunction "1_1") (pintype "passive"))
      (node (ref "C9") (pin "2") (pinfunction "2_2") (pintype "passive"))
      (node (ref "ENCODER1") (pin "1") (pinfunction "GND_1") (pintype "bidirectional"))
      (node (ref "ENCODER2") (pin "1") (pinfunction "GND_1") (pintype "bidirectional"))
      (node (ref "ENCODER3") (pin "1") (pinfunction "GND_1") (pintype "bidirectional"))
      (node (ref "ENCODER4") (pin "1") (pinfunction "GND_1") (pintype "bidirectional"))
      (node (ref "ENCODER5") (pin "1") (pinfunction "GND_1") (pintype "bidirectional"))
      (node (ref "ENCODER6") (pin "1") (pinfunction "GND_1") (pintype "bidirectional"))
      (node (ref "FAN") (pin "1") (pinfunction "1_1") (pintype "bidirectional"))
      (node (ref "GND") (pin "P$1") (pinfunction "P$1_P$1") (pintype "bidirectional"))
      (node (ref "GROUND") (pin "P$1") (pinfunction "P$1_P$1") (pintype "bidirectional"))
      (node (ref "J2") (pin "P3") (pinfunction "~{EXTDBG}_P3") (pintype "bidirectional"))
      (node (ref "J2") (pin "P5") (pinfunction "GND_P5") (pintype "bidirectional"))
      (node (ref "MAINLINE_CURRENT") (pin "2") (pinfunction "GND_2") (pintype "bidirectional"))
      (node (ref "MAINLINE_CURRENT") (pin "4") (pinfunction "GND_4") (pintype "bidirectional"))
      (node (ref "MAINLINE_CURRENT") (pin "7") (pinfunction "GND_7") (pintype "bidirectional"))
      (node (ref "MOTOR1_HB") (pin "23") (pinfunction "GND_23") (pintype "bidirectional"))
      (node (ref "MOTOR1_HB") (pin "24") (pinfunction "GND_24") (pintype "bidirectional"))
      (node (ref "MOTOR1_HB") (pin "25") (pinfunction "GND_25") (pintype "bidirectional"))
      (node (ref "MOTOR1_HB") (pin "26") (pinfunction "GND_26") (pintype "bidirectional"))
      (node (ref "MOTOR1_HB") (pin "5") (pinfunction "GND_5") (pintype "bidirectional"))
      (node (ref "MOTOR1_HB") (pin "6") (pinfunction "GND_6") (pintype "bidirectional"))
      (node (ref "MOTOR1_HB") (pin "7") (pinfunction "GND_7") (pintype "bidirectional"))
      (node (ref "MOTOR1_HB") (pin "8") (pinfunction "GND_8") (pintype "bidirectional"))
      (node (ref "MOTOR2_HB") (pin "23") (pinfunction "GND_23") (pintype "bidirectional"))
      (node (ref "MOTOR2_HB") (pin "24") (pinfunction "GND_24") (pintype "bidirectional"))
      (node (ref "MOTOR2_HB") (pin "25") (pinfunction "GND_25") (pintype "bidirectional"))
      (node (ref "MOTOR2_HB") (pin "26") (pinfunction "GND_26") (pintype "bidirectional"))
      (node (ref "MOTOR2_HB") (pin "5") (pinfunction "GND_5") (pintype "bidirectional"))
      (node (ref "MOTOR2_HB") (pin "6") (pinfunction "GND_6") (pintype "bidirectional"))
      (node (ref "MOTOR2_HB") (pin "7") (pinfunction "GND_7") (pintype "bidirectional"))
      (node (ref "MOTOR2_HB") (pin "8") (pinfunction "GND_8") (pintype "bidirectional"))
      (node (ref "MOTOR3_HB") (pin "23") (pinfunction "GND_23") (pintype "bidirectional"))
      (node (ref "MOTOR3_HB") (pin "24") (pinfunction "GND_24") (pintype "bidirectional"))
      (node (ref "MOTOR3_HB") (pin "25") (pinfunction "GND_25") (pintype "bidirectional"))
      (node (ref "MOTOR3_HB") (pin "26") (pinfunction "GND_26") (pintype "bidirectional"))
      (node (ref "MOTOR3_HB") (pin "5") (pinfunction "GND_5") (pintype "bidirectional"))
      (node (ref "MOTOR3_HB") (pin "6") (pinfunction "GND_6") (pintype "bidirectional"))
      (node (ref "MOTOR3_HB") (pin "7") (pinfunction "GND_7") (pintype "bidirectional"))
      (node (ref "MOTOR3_HB") (pin "8") (pinfunction "GND_8") (pintype "bidirectional"))
      (node (ref "MOTOR4_HB") (pin "23") (pinfunction "GND_23") (pintype "bidirectional"))
      (node (ref "MOTOR4_HB") (pin "24") (pinfunction "GND_24") (pintype "bidirectional"))
      (node (ref "MOTOR4_HB") (pin "25") (pinfunction "GND_25") (pintype "bidirectional"))
      (node (ref "MOTOR4_HB") (pin "26") (pinfunction "GND_26") (pintype "bidirectional"))
      (node (ref "MOTOR4_HB") (pin "5") (pinfunction "GND_5") (pintype "bidirectional"))
      (node (ref "MOTOR4_HB") (pin "6") (pinfunction "GND_6") (pintype "bidirectional"))
      (node (ref "MOTOR4_HB") (pin "7") (pinfunction "GND_7") (pintype "bidirectional"))
      (node (ref "MOTOR4_HB") (pin "8") (pinfunction "GND_8") (pintype "bidirectional"))
      (node (ref "MOTOR5_HB") (pin "23") (pinfunction "GND_23") (pintype "bidirectional"))
      (node (ref "MOTOR5_HB") (pin "24") (pinfunction "GND_24") (pintype "bidirectional"))
      (node (ref "MOTOR5_HB") (pin "25") (pinfunction "GND_25") (pintype "bidirectional"))
      (node (ref "MOTOR5_HB") (pin "26") (pinfunction "GND_26") (pintype "bidirectional"))
      (node (ref "MOTOR5_HB") (pin "5") (pinfunction "GND_5") (pintype "bidirectional"))
      (node (ref "MOTOR5_HB") (pin "6") (pinfunction "GND_6") (pintype "bidirectional"))
      (node (ref "MOTOR5_HB") (pin "7") (pinfunction "GND_7") (pintype "bidirectional"))
      (node (ref "MOTOR5_HB") (pin "8") (pinfunction "GND_8") (pintype "bidirectional"))
      (node (ref "MOTOR6_HB") (pin "23") (pinfunction "GND_23") (pintype "bidirectional"))
      (node (ref "MOTOR6_HB") (pin "24") (pinfunction "GND_24") (pintype "bidirectional"))
      (node (ref "MOTOR6_HB") (pin "25") (pinfunction "GND_25") (pintype "bidirectional"))
      (node (ref "MOTOR6_HB") (pin "26") (pinfunction "GND_26") (pintype "bidirectional"))
      (node (ref "MOTOR6_HB") (pin "5") (pinfunction "GND_5") (pintype "bidirectional"))
      (node (ref "MOTOR6_HB") (pin "6") (pinfunction "GND_6") (pintype "bidirectional"))
      (node (ref "MOTOR6_HB") (pin "7") (pinfunction "GND_7") (pintype "bidirectional"))
      (node (ref "MOTOR6_HB") (pin "8") (pinfunction "GND_8") (pintype "bidirectional"))
      (node (ref "MOTOR7_HB") (pin "23") (pinfunction "GND_23") (pintype "bidirectional"))
      (node (ref "MOTOR7_HB") (pin "24") (pinfunction "GND_24") (pintype "bidirectional"))
      (node (ref "MOTOR7_HB") (pin "25") (pinfunction "GND_25") (pintype "bidirectional"))
      (node (ref "MOTOR7_HB") (pin "26") (pinfunction "GND_26") (pintype "bidirectional"))
      (node (ref "MOTOR7_HB") (pin "5") (pinfunction "GND_5") (pintype "bidirectional"))
      (node (ref "MOTOR7_HB") (pin "6") (pinfunction "GND_6") (pintype "bidirectional"))
      (node (ref "MOTOR7_HB") (pin "7") (pinfunction "GND_7") (pintype "bidirectional"))
      (node (ref "MOTOR7_HB") (pin "8") (pinfunction "GND_8") (pintype "bidirectional"))
      (node (ref "MOTOR8_HB") (pin "23") (pinfunction "GND_23") (pintype "bidirectional"))
      (node (ref "MOTOR8_HB") (pin "24") (pinfunction "GND_24") (pintype "bidirectional"))
      (node (ref "MOTOR8_HB") (pin "25") (pinfunction "GND_25") (pintype "bidirectional"))
      (node (ref "MOTOR8_HB") (pin "26") (pinfunction "GND_26") (pintype "bidirectional"))
      (node (ref "MOTOR8_HB") (pin "5") (pinfunction "GND_5") (pintype "bidirectional"))
      (node (ref "MOTOR8_HB") (pin "6") (pinfunction "GND_6") (pintype "bidirectional"))
      (node (ref "MOTOR8_HB") (pin "7") (pinfunction "GND_7") (pintype "bidirectional"))
      (node (ref "MOTOR8_HB") (pin "8") (pinfunction "GND_8") (pintype "bidirectional"))
      (node (ref "PWM_DRIVER") (pin "1") (pinfunction "A0_1") (pintype "bidirectional"))
      (node (ref "PWM_DRIVER") (pin "14") (pinfunction "GND_14") (pintype "power_in"))
      (node (ref "PWM_DRIVER") (pin "2") (pinfunction "A1_2") (pintype "bidirectional"))
      (node (ref "PWM_DRIVER") (pin "24") (pinfunction "A5_24") (pintype "bidirectional"))
      (node (ref "PWM_DRIVER") (pin "25") (pinfunction "EXTCLK_25") (pintype "input"))
      (node (ref "PWM_DRIVER") (pin "3") (pinfunction "A2_3") (pintype "bidirectional"))
      (node (ref "PWM_DRIVER") (pin "4") (pinfunction "A3_4") (pintype "bidirectional"))
      (node (ref "PWM_DRIVER") (pin "5") (pinfunction "A4_5") (pintype "bidirectional"))
      (node (ref "R10") (pin "2") (pinfunction "2_2") (pintype "passive"))
      (node (ref "R11") (pin "2") (pinfunction "2_2") (pintype "passive"))
      (node (ref "R14") (pin "1") (pinfunction "1_1") (pintype "passive"))
      (node (ref "R18") (pin "1") (pinfunction "1_1") (pintype "passive"))
      (node (ref "R19") (pin "2") (pinfunction "2_2") (pintype "passive"))
      (node (ref "R20") (pin "1") (pinfunction "1_1") (pintype "passive"))
      (node (ref "R49") (pin "1") (pinfunction "1_1") (pintype "passive"))
      (node (ref "R50") (pin "1") (pinfunction "1_1") (pintype "passive"))
      (node (ref "R51") (pin "1") (pinfunction "1_1") (pintype "passive"))
      (node (ref "R52") (pin "1") (pinfunction "1_1") (pintype "passive"))
      (node (ref "R53") (pin "1") (pinfunction "1_1") (pintype "passive"))
      (node (ref "R54") (pin "2") (pinfunction "2_2") (pintype "passive"))
      (node (ref "R55") (pin "2") (pinfunction "2_2") (pintype "passive"))
      (node (ref "R56") (pin "2") (pinfunction "2_2") (pintype "passive"))
      (node (ref "R57") (pin "2") (pinfunction "2_2") (pintype "passive"))
      (node (ref "R58") (pin "1") (pinfunction "1_1") (pintype "passive"))
      (node (ref "R60") (pin "1") (pinfunction "1_1") (pintype "passive"))
      (node (ref "R61") (pin "1") (pinfunction "1_1") (pintype "passive"))
      (node (ref "R62") (pin "1") (pinfunction "1_1") (pintype "passive"))
      (node (ref "R63") (pin "1") (pinfunction "1_1") (pintype "passive"))
      (node (ref "R64") (pin "1") (pinfunction "1_1") (pintype "passive"))
      (node (ref "R65") (pin "1") (pinfunction "1_1") (pintype "passive"))
      (node (ref "R66") (pin "1") (pinfunction "1_1") (pintype "passive"))
      (node (ref "R67") (pin "1") (pinfunction "1_1") (pintype "passive"))
      (node (ref "R68") (pin "1") (pinfunction "1_1") (pintype "passive"))
      (node (ref "R69") (pin "1") (pinfunction "1_1") (pintype "passive"))
      (node (ref "R9") (pin "1") (pinfunction "1_1") (pintype "passive"))
      (node (ref "S1") (pin "P$1") (pinfunction "0_P$1") (pintype "passive"))
      (node (ref "S1") (pin "P$2") (pinfunction "0_P$2") (pintype "passive"))
      (node (ref "TRANSISTOR_DRIVER") (pin "1") (pinfunction "GND_1") (pintype "bidirectional"))
      (node (ref "U1") (pin "P$10") (pinfunction "GNDA_P$10") (pintype "bidirectional"))
      (node (ref "U1") (pin "P$114") (pinfunction "GND_P$114") (pintype "bidirectional"))
      (node (ref "U1") (pin "P$17") (pinfunction "GND_P$17") (pintype "bidirectional"))
      (node (ref "U1") (pin "P$48") (pinfunction "GND_P$48") (pintype "bidirectional"))
      (node (ref "U1") (pin "P$55") (pinfunction "GND_P$55") (pintype "bidirectional"))
      (node (ref "U1") (pin "P$58") (pinfunction "GND_P$58") (pintype "bidirectional"))
      (node (ref "U1") (pin "P$80") (pinfunction "GND_P$80") (pintype "bidirectional"))
      (node (ref "U4") (pin "5") (pinfunction "GND_5") (pintype "bidirectional"))
      (node (ref "U5") (pin "5") (pinfunction "GND_5") (pintype "bidirectional"))
      (node (ref "U6") (pin "5") (pinfunction "GND_5") (pintype "bidirectional"))
      (node (ref "U7") (pin "5") (pinfunction "GND_5") (pintype "bidirectional"))
      (node (ref "U8") (pin "5") (pinfunction "GND_5") (pintype "bidirectional"))
      (node (ref "U9") (pin "5") (pinfunction "GND_5") (pintype "bidirectional"))
    )
    (net (code "18") (name "LED1") (class "Default")
      (node (ref "D1") (pin "A") (pinfunction "A_A") (pintype "passive"))
      (node (ref "U1") (pin "P$23") (pinfunction "PC6_P$23") (pintype "bidirectional"))
    )
    (net (code "19") (name "LED2") (class "Default")
      (node (ref "D2") (pin "A") (pinfunction "A_A") (pintype "passive"))
      (node (ref "U1") (pin "P$22") (pinfunction "PC7_P$22") (pintype "bidirectional"))
    )
    (net (code "20") (name "LED3") (class "Default")
      (node (ref "D3") (pin "A") (pinfunction "A_A") (pintype "passive"))
      (node (ref "U1") (pin "P$21") (pinfunction "PK3_P$21") (pintype "bidirectional"))
    )
    (net (code "21") (name "LED4") (class "Default")
      (node (ref "D4") (pin "A") (pinfunction "A_A") (pintype "passive"))
      (node (ref "U1") (pin "P$20") (pinfunction "PK2_P$20") (pintype "bidirectional"))
    )
    (net (code "22") (name "LED5") (class "Default")
      (node (ref "D5") (pin "A") (pinfunction "A_A") (pintype "passive"))
      (node (ref "U1") (pin "P$19") (pinfunction "PK1_P$19") (pintype "bidirectional"))
    )
    (net (code "23") (name "LED6") (class "Default")
      (node (ref "D6") (pin "A") (pinfunction "A_A") (pintype "passive"))
      (node (ref "U1") (pin "P$18") (pinfunction "PK0_P$18") (pintype "bidirectional"))
    )
    (net (code "24") (name "LIMIT_SWITCH_1") (class "Default")
      (node (ref "LIMIT_SWITCH_1") (pin "1") (pinfunction "1_1") (pintype "bidirectional"))
      (node (ref "R51") (pin "2") (pinfunction "2_2") (pintype "passive"))
      (node (ref "U1") (pin "P$32") (pinfunction "PH3_P$32") (pintype "bidirectional"))
    )
    (net (code "25") (name "LIMIT_SWITCH_2") (class "Default")
      (node (ref "LIMIT_SWITCH_2") (pin "1") (pinfunction "1_1") (pintype "bidirectional"))
      (node (ref "R52") (pin "2") (pinfunction "2_2") (pintype "passive"))
      (node (ref "U1") (pin "P$31") (pinfunction "PH2_P$31") (pintype "bidirectional"))
    )
    (net (code "26") (name "LIMIT_SWITCH_3") (class "Default")
      (node (ref "LIMIT_SWITCH_3") (pin "1") (pinfunction "1_1") (pintype "bidirectional"))
      (node (ref "R53") (pin "2") (pinfunction "2_2") (pintype "passive"))
      (node (ref "U1") (pin "P$30") (pinfunction "PH1_P$30") (pintype "bidirectional"))
    )
    (net (code "27") (name "LOGIC_3.3V") (class "Default")
      (node (ref "3.3V") (pin "A") (pinfunction "A_A") (pintype "passive"))
      (node (ref "3.3V_DCDC_OKI") (pin "3") (pinfunction "VOUT_3") (pintype "bidirectional"))
      (node (ref "C1") (pin "1") (pinfunction "1_1") (pintype "passive"))
      (node (ref "C10") (pin "1") (pinfunction "1_1") (pintype "passive"))
      (node (ref "C11") (pin "1") (pinfunction "1_1") (pintype "passive"))
      (node (ref "C2") (pin "1") (pinfunction "1_1") (pintype "passive"))
      (node (ref "C24") (pin "2") (pinfunction "2_2") (pintype "passive"))
      (node (ref "C27") (pin "2") (pinfunction "2_2") (pintype "passive"))
      (node (ref "C3") (pin "1") (pinfunction "1_1") (pintype "passive"))
      (node (ref "C30") (pin "2") (pinfunction "2_2") (pintype "passive"))
      (node (ref "C33") (pin "2") (pinfunction "2_2") (pintype "passive"))
      (node (ref "C36") (pin "2") (pinfunction "2_2") (pintype "passive"))
      (node (ref "C39") (pin "2") (pinfunction "2_2") (pintype "passive"))
      (node (ref "C4") (pin "1") (pinfunction "1_1") (pintype "passive"))
      (node (ref "C74") (pin "1") (pinfunction "1_1") (pintype "passive"))
      (node (ref "C8") (pin "1") (pinfunction "1_1") (pintype "passive"))
      (node (ref "C9") (pin "1") (pinfunction "1_1") (pintype "passive"))
      (node (ref "ENCODER1") (pin "3") (pinfunction "VCC_3") (pintype "bidirectional"))
      (node (ref "ENCODER2") (pin "3") (pinfunction "VCC_3") (pintype "bidirectional"))
      (node (ref "ENCODER3") (pin "3") (pinfunction "VCC_3") (pintype "bidirectional"))
      (node (ref "ENCODER4") (pin "3") (pinfunction "VCC_3") (pintype "bidirectional"))
      (node (ref "ENCODER5") (pin "3") (pinfunction "VCC_3") (pintype "bidirectional"))
      (node (ref "ENCODER6") (pin "3") (pinfunction "VCC_3") (pintype "bidirectional"))
      (node (ref "FAN") (pin "2") (pinfunction "2_2") (pintype "bidirectional"))
      (node (ref "J2") (pin "P1") (pinfunction "VTARGET_P1") (pintype "bidirectional"))
      (node (ref "LIMIT_SWITCH_1") (pin "2") (pinfunction "2_2") (pintype "bidirectional"))
      (node (ref "LIMIT_SWITCH_2") (pin "2") (pinfunction "2_2") (pintype "bidirectional"))
      (node (ref "LIMIT_SWITCH_3") (pin "2") (pinfunction "2_2") (pintype "bidirectional"))
      (node (ref "MAINLINE_CURRENT") (pin "1") (pinfunction "VCC_1") (pintype "bidirectional"))
      (node (ref "OE_PULLUP") (pin "1") (pinfunction "1_1") (pintype "passive"))
      (node (ref "PWM_DRIVER") (pin "28") (pinfunction "VDD_28") (pintype "power_in"))
      (node (ref "R1") (pin "1") (pinfunction "1_1") (pintype "passive"))
      (node (ref "R12") (pin "2") (pinfunction "2_2") (pintype "passive"))
      (node (ref "R13") (pin "2") (pinfunction "2_2") (pintype "passive"))
      (node (ref "R17") (pin "1") (pinfunction "1_1") (pintype "passive"))
      (node (ref "R2") (pin "1") (pinfunction "1_1") (pintype "passive"))
      (node (ref "R3") (pin "1") (pinfunction "1_1") (pintype "passive"))
      (node (ref "R4") (pin "1") (pinfunction "1_1") (pintype "passive"))
      (node (ref "S2") (pin "P$1") (pinfunction "P_P$1") (pintype "passive"))
      (node (ref "S3") (pin "P$1") (pinfunction "P_P$1") (pintype "passive"))
      (node (ref "S4") (pin "P$1") (pinfunction "P_P$1") (pintype "passive"))
      (node (ref "S5") (pin "P$2") (pinfunction "P_P$2") (pintype "passive"))
      (node (ref "SCL_PULLUP") (pin "1") (pinfunction "1_1") (pintype "passive"))
      (node (ref "SDA_PULLUP") (pin "1") (pinfunction "1_1") (pintype "passive"))
      (node (ref "U1") (pin "P$101") (pinfunction "VDD_P$101") (pintype "bidirectional"))
      (node (ref "U1") (pin "P$113") (pinfunction "VDD_P$113") (pintype "bidirectional"))
      (node (ref "U1") (pin "P$122") (pinfunction "VDD_P$122") (pintype "bidirectional"))
      (node (ref "U1") (pin "P$16") (pinfunction "VDD_P$16") (pintype "bidirectional"))
      (node (ref "U1") (pin "P$26") (pinfunction "VDD_P$26") (pintype "bidirectional"))
      (node (ref "U1") (pin "P$28") (pinfunction "VDD_P$28") (pintype "bidirectional"))
      (node (ref "U1") (pin "P$39") (pinfunction "VDD_P$39") (pintype "bidirectional"))
      (node (ref "U1") (pin "P$47") (pinfunction "VDD_P$47") (pintype "bidirectional"))
      (node (ref "U1") (pin "P$51") (pinfunction "VDD_P$51") (pintype "bidirectional"))
      (node (ref "U1") (pin "P$52") (pinfunction "VDD_P$52") (pintype "bidirectional"))
      (node (ref "U1") (pin "P$69") (pinfunction "VDD_P$69") (pintype "bidirectional"))
      (node (ref "U1") (pin "P$7") (pinfunction "VDD_P$7") (pintype "bidirectional"))
      (node (ref "U1") (pin "P$79") (pinfunction "VDD_P$79") (pintype "bidirectional"))
      (node (ref "U1") (pin "P$8") (pinfunction "VDDA_P$8") (pintype "bidirectional"))
      (node (ref "U1") (pin "P$9") (pinfunction "VREFA+_P$9") (pintype "bidirectional"))
      (node (ref "U1") (pin "P$90") (pinfunction "VDD_P$90") (pintype "bidirectional"))
      (node (ref "U2") (pin "P$2") (pinfunction "P$2_P$2") (pintype "bidirectional"))
      (node (ref "U2") (pin "P$7") (pinfunction "P$7_P$7") (pintype "bidirectional"))
      (node (ref "U4") (pin "8") (pinfunction "VCC_8") (pintype "bidirectional"))
      (node (ref "U5") (pin "8") (pinfunction "VCC_8") (pintype "bidirectional"))
      (node (ref "U6") (pin "8") (pinfunction "VCC_8") (pintype "bidirectional"))
      (node (ref "U7") (pin "8") (pinfunction "VCC_8") (pintype "bidirectional"))
      (node (ref "U8") (pin "8") (pinfunction "VCC_8") (pintype "bidirectional"))
      (node (ref "U9") (pin "8") (pinfunction "VCC_8") (pintype "bidirectional"))
    )
    (net (code "28") (name "MAINLINE_CURRENT_SENSOR") (class "Default")
      (node (ref "C75") (pin "1") (pinfunction "1_1") (pintype "passive"))
      (node (ref "R59") (pin "1") (pinfunction "1_1") (pintype "passive"))
      (node (ref "U1") (pin "P$121") (pinfunction "PB4_P$121") (pintype "bidirectional"))
    )
    (net (code "29") (name "MASTER_POWER_ENABLE") (class "Default")
      (node (ref "R58") (pin "2") (pinfunction "2_2") (pintype "passive"))
      (node (ref "TRANSISTOR_DRIVER") (pin "4") (pinfunction "IN_4") (pintype "bidirectional"))
      (node (ref "U1") (pin "P$109") (pinfunction "PN2_P$109") (pintype "bidirectional"))
    )
    (net (code "30") (name "MOTOR1_1") (class "Default")
      (node (ref "MOTOR1") (pin "C2") (pinfunction "P$1_C2") (pintype "bidirectional"))
      (node (ref "MOTOR1_HB") (pin "1") (pinfunction "OUT1_1") (pintype "bidirectional"))
      (node (ref "MOTOR1_HB") (pin "2") (pinfunction "OUT1_2") (pintype "bidirectional"))
      (node (ref "MOTOR1_HB") (pin "3") (pinfunction "OUT1_3") (pintype "bidirectional"))
      (node (ref "MOTOR1_HB") (pin "33") (pinfunction "OUT1_33") (pintype "bidirectional"))
      (node (ref "MOTOR1_HB") (pin "34") (pinfunction "OUT1_34") (pintype "bidirectional"))
      (node (ref "MOTOR1_HB") (pin "35") (pinfunction "OUT1_35") (pintype "bidirectional"))
      (node (ref "MOTOR1_HB") (pin "36") (pinfunction "OUT1_36") (pintype "bidirectional"))
      (node (ref "MOTOR1_HB") (pin "4") (pinfunction "OUT1_4") (pintype "bidirectional"))
    )
    (net (code "31") (name "MOTOR1_2") (class "Default")
      (node (ref "MOTOR1") (pin "C1") (pinfunction "P$1_C1") (pintype "bidirectional"))
      (node (ref "MOTOR1_HB") (pin "15") (pinfunction "OUT2_15") (pintype "bidirectional"))
      (node (ref "MOTOR1_HB") (pin "16") (pinfunction "OUT2_16") (pintype "bidirectional"))
      (node (ref "MOTOR1_HB") (pin "17") (pinfunction "OUT2_17") (pintype "bidirectional"))
      (node (ref "MOTOR1_HB") (pin "18") (pinfunction "OUT2_18") (pintype "bidirectional"))
      (node (ref "MOTOR1_HB") (pin "19") (pinfunction "OUT2_19") (pintype "bidirectional"))
      (node (ref "MOTOR1_HB") (pin "20") (pinfunction "OUT2_20") (pintype "bidirectional"))
      (node (ref "MOTOR1_HB") (pin "21") (pinfunction "OUT2_21") (pintype "bidirectional"))
      (node (ref "MOTOR1_HB") (pin "22") (pinfunction "OUT2_22") (pintype "bidirectional"))
    )
    (net (code "32") (name "MOTOR1_CURRENT_SENSOR") (class "Default")
      (node (ref "C26") (pin "1") (pinfunction "1_1") (pintype "passive"))
      (node (ref "U1") (pin "P$123") (pinfunction "PE4_P$123") (pintype "bidirectional"))
      (node (ref "U8") (pin "7") (pinfunction "VIOUT_7") (pintype "bidirectional"))
    )
    (net (code "33") (name "MOTOR1_ENABLE") (class "Default")
      (node (ref "MOTOR1_HB") (pin "27") (pinfunction "INH_27") (pintype "bidirectional"))
      (node (ref "U1") (pin "P$96") (pinfunction "PB1_P$96") (pintype "bidirectional"))
    )
    (net (code "34") (name "MOTOR1_POWER") (class "Default")
      (node (ref "C22") (pin "2") (pinfunction "2_2") (pintype "passive"))
      (node (ref "C23") (pin "2") (pinfunction "2_2") (pintype "passive"))
      (node (ref "MOTOR1_HB") (pin "11") (pinfunction "VS_11") (pintype "bidirectional"))
      (node (ref "MOTOR1_HB") (pin "12") (pinfunction "VS_12") (pintype "bidirectional"))
      (node (ref "MOTOR1_HB") (pin "13") (pinfunction "VS_13") (pintype "bidirectional"))
      (node (ref "MOTOR1_HB") (pin "14") (pinfunction "VS_14") (pintype "bidirectional"))
      (node (ref "MOTOR1_HB") (pin "29") (pinfunction "VS_29") (pintype "bidirectional"))
      (node (ref "MOTOR1_HB") (pin "30") (pinfunction "VS_30") (pintype "bidirectional"))
      (node (ref "MOTOR1_HB") (pin "31") (pinfunction "VS_31") (pintype "bidirectional"))
      (node (ref "MOTOR1_HB") (pin "32") (pinfunction "VS_32") (pintype "bidirectional"))
      (node (ref "U8") (pin "3") (pinfunction "IP-_3") (pintype "bidirectional"))
      (node (ref "U8") (pin "4") (pinfunction "IP-_4") (pintype "bidirectional"))
    )
    (net (code "35") (name "MOTOR1_PWM1") (class "Default")
      (node (ref "MOTOR1_HB") (pin "9") (pinfunction "IN1_9") (pintype "bidirectional"))
      (node (ref "PWM_DRIVER") (pin "6") (pinfunction "PWM0_6") (pintype "output"))
    )
    (net (code "36") (name "MOTOR1_PWM2") (class "Default")
      (node (ref "MOTOR1_HB") (pin "10") (pinfunction "IN2_10") (pintype "bidirectional"))
      (node (ref "PWM_DRIVER") (pin "7") (pinfunction "PWM1_7") (pintype "output"))
    )
    (net (code "37") (name "MOTOR2_1") (class "Default")
      (node (ref "MOTOR2") (pin "C2") (pinfunction "P$1_C2") (pintype "bidirectional"))
      (node (ref "MOTOR2_HB") (pin "1") (pinfunction "OUT1_1") (pintype "bidirectional"))
      (node (ref "MOTOR2_HB") (pin "2") (pinfunction "OUT1_2") (pintype "bidirectional"))
      (node (ref "MOTOR2_HB") (pin "3") (pinfunction "OUT1_3") (pintype "bidirectional"))
      (node (ref "MOTOR2_HB") (pin "33") (pinfunction "OUT1_33") (pintype "bidirectional"))
      (node (ref "MOTOR2_HB") (pin "34") (pinfunction "OUT1_34") (pintype "bidirectional"))
      (node (ref "MOTOR2_HB") (pin "35") (pinfunction "OUT1_35") (pintype "bidirectional"))
      (node (ref "MOTOR2_HB") (pin "36") (pinfunction "OUT1_36") (pintype "bidirectional"))
      (node (ref "MOTOR2_HB") (pin "4") (pinfunction "OUT1_4") (pintype "bidirectional"))
    )
    (net (code "38") (name "MOTOR2_2") (class "Default")
      (node (ref "MOTOR2") (pin "C1") (pinfunction "P$1_C1") (pintype "bidirectional"))
      (node (ref "MOTOR2_HB") (pin "15") (pinfunction "OUT2_15") (pintype "bidirectional"))
      (node (ref "MOTOR2_HB") (pin "16") (pinfunction "OUT2_16") (pintype "bidirectional"))
      (node (ref "MOTOR2_HB") (pin "17") (pinfunction "OUT2_17") (pintype "bidirectional"))
      (node (ref "MOTOR2_HB") (pin "18") (pinfunction "OUT2_18") (pintype "bidirectional"))
      (node (ref "MOTOR2_HB") (pin "19") (pinfunction "OUT2_19") (pintype "bidirectional"))
      (node (ref "MOTOR2_HB") (pin "20") (pinfunction "OUT2_20") (pintype "bidirectional"))
      (node (ref "MOTOR2_HB") (pin "21") (pinfunction "OUT2_21") (pintype "bidirectional"))
      (node (ref "MOTOR2_HB") (pin "22") (pinfunction "OUT2_22") (pintype "bidirectional"))
    )
    (net (code "39") (name "MOTOR2_CURRENT_SENSOR") (class "Default")
      (node (ref "C29") (pin "1") (pinfunction "1_1") (pintype "passive"))
      (node (ref "U1") (pin "P$124") (pinfunction "PE5_P$124") (pintype "bidirectional"))
      (node (ref "U4") (pin "7") (pinfunction "VIOUT_7") (pintype "bidirectional"))
    )
    (net (code "40") (name "MOTOR2_ENABLE") (class "Default")
      (node (ref "MOTOR2_HB") (pin "27") (pinfunction "INH_27") (pintype "bidirectional"))
      (node (ref "U1") (pin "P$110") (pinfunction "PN3_P$110") (pintype "bidirectional"))
    )
    (net (code "41") (name "MOTOR2_POWER") (class "Default")
      (node (ref "C82") (pin "2") (pinfunction "2_2") (pintype "passive"))
      (node (ref "C83") (pin "2") (pinfunction "2_2") (pintype "passive"))
      (node (ref "MOTOR2_HB") (pin "11") (pinfunction "VS_11") (pintype "bidirectional"))
      (node (ref "MOTOR2_HB") (pin "12") (pinfunction "VS_12") (pintype "bidirectional"))
      (node (ref "MOTOR2_HB") (pin "13") (pinfunction "VS_13") (pintype "bidirectional"))
      (node (ref "MOTOR2_HB") (pin "14") (pinfunction "VS_14") (pintype "bidirectional"))
      (node (ref "MOTOR2_HB") (pin "29") (pinfunction "VS_29") (pintype "bidirectional"))
      (node (ref "MOTOR2_HB") (pin "30") (pinfunction "VS_30") (pintype "bidirectional"))
      (node (ref "MOTOR2_HB") (pin "31") (pinfunction "VS_31") (pintype "bidirectional"))
      (node (ref "MOTOR2_HB") (pin "32") (pinfunction "VS_32") (pintype "bidirectional"))
      (node (ref "U4") (pin "3") (pinfunction "IP-_3") (pintype "bidirectional"))
      (node (ref "U4") (pin "4") (pinfunction "IP-_4") (pintype "bidirectional"))
    )
    (net (code "42") (name "MOTOR2_PWM1") (class "Default")
      (node (ref "MOTOR2_HB") (pin "9") (pinfunction "IN1_9") (pintype "bidirectional"))
      (node (ref "PWM_DRIVER") (pin "8") (pinfunction "PWM2_8") (pintype "output"))
    )
    (net (code "43") (name "MOTOR2_PWM2") (class "Default")
      (node (ref "MOTOR2_HB") (pin "10") (pinfunction "IN2_10") (pintype "bidirectional"))
      (node (ref "PWM_DRIVER") (pin "9") (pinfunction "PWM3_9") (pintype "output"))
    )
    (net (code "44") (name "MOTOR3_1") (class "Default")
      (node (ref "MOTOR3") (pin "C2") (pinfunction "P$1_C2") (pintype "bidirectional"))
      (node (ref "MOTOR3_HB") (pin "1") (pinfunction "OUT1_1") (pintype "bidirectional"))
      (node (ref "MOTOR3_HB") (pin "2") (pinfunction "OUT1_2") (pintype "bidirectional"))
      (node (ref "MOTOR3_HB") (pin "3") (pinfunction "OUT1_3") (pintype "bidirectional"))
      (node (ref "MOTOR3_HB") (pin "33") (pinfunction "OUT1_33") (pintype "bidirectional"))
      (node (ref "MOTOR3_HB") (pin "34") (pinfunction "OUT1_34") (pintype "bidirectional"))
      (node (ref "MOTOR3_HB") (pin "35") (pinfunction "OUT1_35") (pintype "bidirectional"))
      (node (ref "MOTOR3_HB") (pin "36") (pinfunction "OUT1_36") (pintype "bidirectional"))
      (node (ref "MOTOR3_HB") (pin "4") (pinfunction "OUT1_4") (pintype "bidirectional"))
    )
    (net (code "45") (name "MOTOR3_2") (class "Default")
      (node (ref "MOTOR3") (pin "C1") (pinfunction "P$1_C1") (pintype "bidirectional"))
      (node (ref "MOTOR3_HB") (pin "15") (pinfunction "OUT2_15") (pintype "bidirectional"))
      (node (ref "MOTOR3_HB") (pin "16") (pinfunction "OUT2_16") (pintype "bidirectional"))
      (node (ref "MOTOR3_HB") (pin "17") (pinfunction "OUT2_17") (pintype "bidirectional"))
      (node (ref "MOTOR3_HB") (pin "18") (pinfunction "OUT2_18") (pintype "bidirectional"))
      (node (ref "MOTOR3_HB") (pin "19") (pinfunction "OUT2_19") (pintype "bidirectional"))
      (node (ref "MOTOR3_HB") (pin "20") (pinfunction "OUT2_20") (pintype "bidirectional"))
      (node (ref "MOTOR3_HB") (pin "21") (pinfunction "OUT2_21") (pintype "bidirectional"))
      (node (ref "MOTOR3_HB") (pin "22") (pinfunction "OUT2_22") (pintype "bidirectional"))
    )
    (net (code "46") (name "MOTOR3_CURRENT_SENSOR") (class "Default")
      (node (ref "C32") (pin "1") (pinfunction "1_1") (pintype "passive"))
      (node (ref "U1") (pin "P$126") (pinfunction "PD5_P$126") (pintype "bidirectional"))
      (node (ref "U5") (pin "7") (pinfunction "VIOUT_7") (pintype "bidirectional"))
    )
    (net (code "47") (name "MOTOR3_ENABLE") (class "Default")
      (node (ref "MOTOR3_HB") (pin "27") (pinfunction "INH_27") (pintype "bidirectional"))
      (node (ref "U1") (pin "P$15") (pinfunction "PE0_P$15") (pintype "bidirectional"))
    )
    (net (code "48") (name "MOTOR3_POWER") (class "Default")
      (node (ref "C78") (pin "2") (pinfunction "2_2") (pintype "passive"))
      (node (ref "C79") (pin "2") (pinfunction "2_2") (pintype "passive"))
      (node (ref "MOTOR3_HB") (pin "11") (pinfunction "VS_11") (pintype "bidirectional"))
      (node (ref "MOTOR3_HB") (pin "12") (pinfunction "VS_12") (pintype "bidirectional"))
      (node (ref "MOTOR3_HB") (pin "13") (pinfunction "VS_13") (pintype "bidirectional"))
      (node (ref "MOTOR3_HB") (pin "14") (pinfunction "VS_14") (pintype "bidirectional"))
      (node (ref "MOTOR3_HB") (pin "29") (pinfunction "VS_29") (pintype "bidirectional"))
      (node (ref "MOTOR3_HB") (pin "30") (pinfunction "VS_30") (pintype "bidirectional"))
      (node (ref "MOTOR3_HB") (pin "31") (pinfunction "VS_31") (pintype "bidirectional"))
      (node (ref "MOTOR3_HB") (pin "32") (pinfunction "VS_32") (pintype "bidirectional"))
      (node (ref "U5") (pin "3") (pinfunction "IP-_3") (pintype "bidirectional"))
      (node (ref "U5") (pin "4") (pinfunction "IP-_4") (pintype "bidirectional"))
    )
    (net (code "49") (name "MOTOR3_PWM1") (class "Default")
      (node (ref "MOTOR3_HB") (pin "9") (pinfunction "IN1_9") (pintype "bidirectional"))
      (node (ref "PWM_DRIVER") (pin "10") (pinfunction "PWM4_10") (pintype "output"))
    )
    (net (code "50") (name "MOTOR3_PWM2") (class "Default")
      (node (ref "MOTOR3_HB") (pin "10") (pinfunction "IN2_10") (pintype "bidirectional"))
      (node (ref "PWM_DRIVER") (pin "11") (pinfunction "PWM5_11") (pintype "output"))
    )
    (net (code "51") (name "MOTOR4_1") (class "Default")
      (node (ref "MOTOR4") (pin "C2") (pinfunction "P$1_C2") (pintype "bidirectional"))
      (node (ref "MOTOR4_HB") (pin "1") (pinfunction "OUT1_1") (pintype "bidirectional"))
      (node (ref "MOTOR4_HB") (pin "2") (pinfunction "OUT1_2") (pintype "bidirectional"))
      (node (ref "MOTOR4_HB") (pin "3") (pinfunction "OUT1_3") (pintype "bidirectional"))
      (node (ref "MOTOR4_HB") (pin "33") (pinfunction "OUT1_33") (pintype "bidirectional"))
      (node (ref "MOTOR4_HB") (pin "34") (pinfunction "OUT1_34") (pintype "bidirectional"))
      (node (ref "MOTOR4_HB") (pin "35") (pinfunction "OUT1_35") (pintype "bidirectional"))
      (node (ref "MOTOR4_HB") (pin "36") (pinfunction "OUT1_36") (pintype "bidirectional"))
      (node (ref "MOTOR4_HB") (pin "4") (pinfunction "OUT1_4") (pintype "bidirectional"))
    )
    (net (code "52") (name "MOTOR4_2") (class "Default")
      (node (ref "MOTOR4") (pin "C1") (pinfunction "P$1_C1") (pintype "bidirectional"))
      (node (ref "MOTOR4_HB") (pin "15") (pinfunction "OUT2_15") (pintype "bidirectional"))
      (node (ref "MOTOR4_HB") (pin "16") (pinfunction "OUT2_16") (pintype "bidirectional"))
      (node (ref "MOTOR4_HB") (pin "17") (pinfunction "OUT2_17") (pintype "bidirectional"))
      (node (ref "MOTOR4_HB") (pin "18") (pinfunction "OUT2_18") (pintype "bidirectional"))
      (node (ref "MOTOR4_HB") (pin "19") (pinfunction "OUT2_19") (pintype "bidirectional"))
      (node (ref "MOTOR4_HB") (pin "20") (pinfunction "OUT2_20") (pintype "bidirectional"))
      (node (ref "MOTOR4_HB") (pin "21") (pinfunction "OUT2_21") (pintype "bidirectional"))
      (node (ref "MOTOR4_HB") (pin "22") (pinfunction "OUT2_22") (pintype "bidirectional"))
    )
    (net (code "53") (name "MOTOR4_CURRENT_SENSOR") (class "Default")
      (node (ref "C41") (pin "1") (pinfunction "1_1") (pintype "passive"))
      (node (ref "U1") (pin "P$127") (pinfunction "PD6_P$127") (pintype "bidirectional"))
      (node (ref "U9") (pin "7") (pinfunction "VIOUT_7") (pintype "bidirectional"))
    )
    (net (code "54") (name "MOTOR4_ENABLE") (class "Default")
      (node (ref "MOTOR4_HB") (pin "27") (pinfunction "INH_27") (pintype "bidirectional"))
      (node (ref "U1") (pin "P$116") (pinfunction "PJ0_P$116") (pintype "bidirectional"))
    )
    (net (code "55") (name "MOTOR4_POWER") (class "Default")
      (node (ref "C20") (pin "2") (pinfunction "2_2") (pintype "passive"))
      (node (ref "C21") (pin "2") (pinfunction "2_2") (pintype "passive"))
      (node (ref "MOTOR4_HB") (pin "11") (pinfunction "VS_11") (pintype "bidirectional"))
      (node (ref "MOTOR4_HB") (pin "12") (pinfunction "VS_12") (pintype "bidirectional"))
      (node (ref "MOTOR4_HB") (pin "13") (pinfunction "VS_13") (pintype "bidirectional"))
      (node (ref "MOTOR4_HB") (pin "14") (pinfunction "VS_14") (pintype "bidirectional"))
      (node (ref "MOTOR4_HB") (pin "29") (pinfunction "VS_29") (pintype "bidirectional"))
      (node (ref "MOTOR4_HB") (pin "30") (pinfunction "VS_30") (pintype "bidirectional"))
      (node (ref "MOTOR4_HB") (pin "31") (pinfunction "VS_31") (pintype "bidirectional"))
      (node (ref "MOTOR4_HB") (pin "32") (pinfunction "VS_32") (pintype "bidirectional"))
      (node (ref "U9") (pin "3") (pinfunction "IP-_3") (pintype "bidirectional"))
      (node (ref "U9") (pin "4") (pinfunction "IP-_4") (pintype "bidirectional"))
    )
    (net (code "56") (name "MOTOR4_PWM1") (class "Default")
      (node (ref "MOTOR4_HB") (pin "9") (pinfunction "IN1_9") (pintype "bidirectional"))
      (node (ref "PWM_DRIVER") (pin "12") (pinfunction "PWM6_12") (pintype "output"))
    )
    (net (code "57") (name "MOTOR4_PWM2") (class "Default")
      (node (ref "MOTOR4_HB") (pin "10") (pinfunction "IN2_10") (pintype "bidirectional"))
      (node (ref "PWM_DRIVER") (pin "13") (pinfunction "PWM7_13") (pintype "output"))
    )
    (net (code "58") (name "MOTOR5_1") (class "Default")
      (node (ref "MOTOR5") (pin "C2") (pinfunction "P$1_C2") (pintype "bidirectional"))
      (node (ref "MOTOR5_HB") (pin "1") (pinfunction "OUT1_1") (pintype "bidirectional"))
      (node (ref "MOTOR5_HB") (pin "2") (pinfunction "OUT1_2") (pintype "bidirectional"))
      (node (ref "MOTOR5_HB") (pin "3") (pinfunction "OUT1_3") (pintype "bidirectional"))
      (node (ref "MOTOR5_HB") (pin "33") (pinfunction "OUT1_33") (pintype "bidirectional"))
      (node (ref "MOTOR5_HB") (pin "34") (pinfunction "OUT1_34") (pintype "bidirectional"))
      (node (ref "MOTOR5_HB") (pin "35") (pinfunction "OUT1_35") (pintype "bidirectional"))
      (node (ref "MOTOR5_HB") (pin "36") (pinfunction "OUT1_36") (pintype "bidirectional"))
      (node (ref "MOTOR5_HB") (pin "4") (pinfunction "OUT1_4") (pintype "bidirectional"))
    )
    (net (code "59") (name "MOTOR5_2") (class "Default")
      (node (ref "MOTOR5") (pin "C1") (pinfunction "P$1_C1") (pintype "bidirectional"))
      (node (ref "MOTOR5_HB") (pin "15") (pinfunction "OUT2_15") (pintype "bidirectional"))
      (node (ref "MOTOR5_HB") (pin "16") (pinfunction "OUT2_16") (pintype "bidirectional"))
      (node (ref "MOTOR5_HB") (pin "17") (pinfunction "OUT2_17") (pintype "bidirectional"))
      (node (ref "MOTOR5_HB") (pin "18") (pinfunction "OUT2_18") (pintype "bidirectional"))
      (node (ref "MOTOR5_HB") (pin "19") (pinfunction "OUT2_19") (pintype "bidirectional"))
      (node (ref "MOTOR5_HB") (pin "20") (pinfunction "OUT2_20") (pintype "bidirectional"))
      (node (ref "MOTOR5_HB") (pin "21") (pinfunction "OUT2_21") (pintype "bidirectional"))
      (node (ref "MOTOR5_HB") (pin "22") (pinfunction "OUT2_22") (pintype "bidirectional"))
    )
    (net (code "60") (name "MOTOR5_CURRENT_SENSOR") (class "Default")
      (node (ref "C35") (pin "1") (pinfunction "1_1") (pintype "passive"))
      (node (ref "U1") (pin "P$1") (pinfunction "PD0_P$1") (pintype "bidirectional"))
      (node (ref "U6") (pin "7") (pinfunction "VIOUT_7") (pintype "bidirectional"))
    )
    (net (code "61") (name "MOTOR5_ENABLE") (class "Default")
      (node (ref "MOTOR5_HB") (pin "27") (pinfunction "INH_27") (pintype "bidirectional"))
      (node (ref "U1") (pin "P$117") (pinfunction "PJ1_P$117") (pintype "bidirectional"))
    )
    (net (code "62") (name "MOTOR5_POWER") (class "Default")
      (node (ref "C80") (pin "2") (pinfunction "2_2") (pintype "passive"))
      (node (ref "C81") (pin "2") (pinfunction "2_2") (pintype "passive"))
      (node (ref "MOTOR5_HB") (pin "11") (pinfunction "VS_11") (pintype "bidirectional"))
      (node (ref "MOTOR5_HB") (pin "12") (pinfunction "VS_12") (pintype "bidirectional"))
      (node (ref "MOTOR5_HB") (pin "13") (pinfunction "VS_13") (pintype "bidirectional"))
      (node (ref "MOTOR5_HB") (pin "14") (pinfunction "VS_14") (pintype "bidirectional"))
      (node (ref "MOTOR5_HB") (pin "29") (pinfunction "VS_29") (pintype "bidirectional"))
      (node (ref "MOTOR5_HB") (pin "30") (pinfunction "VS_30") (pintype "bidirectional"))
      (node (ref "MOTOR5_HB") (pin "31") (pinfunction "VS_31") (pintype "bidirectional"))
      (node (ref "MOTOR5_HB") (pin "32") (pinfunction "VS_32") (pintype "bidirectional"))
      (node (ref "U6") (pin "3") (pinfunction "IP-_3") (pintype "bidirectional"))
      (node (ref "U6") (pin "4") (pinfunction "IP-_4") (pintype "bidirectional"))
    )
    (net (code "63") (name "MOTOR5_PWM1") (class "Default")
      (node (ref "MOTOR5_HB") (pin "9") (pinfunction "IN1_9") (pintype "bidirectional"))
      (node (ref "PWM_DRIVER") (pin "15") (pinfunction "PWM8_15") (pintype "output"))
    )
    (net (code "64") (name "MOTOR5_PWM2") (class "Default")
      (node (ref "MOTOR5_HB") (pin "10") (pinfunction "IN2_10") (pintype "bidirectional"))
      (node (ref "PWM_DRIVER") (pin "16") (pinfunction "PWM9_16") (pintype "output"))
    )
    (net (code "65") (name "MOTOR6_1") (class "Default")
      (node (ref "MOTOR6") (pin "C2") (pinfunction "P$1_C2") (pintype "bidirectional"))
      (node (ref "MOTOR6_HB") (pin "1") (pinfunction "OUT1_1") (pintype "bidirectional"))
      (node (ref "MOTOR6_HB") (pin "2") (pinfunction "OUT1_2") (pintype "bidirectional"))
      (node (ref "MOTOR6_HB") (pin "3") (pinfunction "OUT1_3") (pintype "bidirectional"))
      (node (ref "MOTOR6_HB") (pin "33") (pinfunction "OUT1_33") (pintype "bidirectional"))
      (node (ref "MOTOR6_HB") (pin "34") (pinfunction "OUT1_34") (pintype "bidirectional"))
      (node (ref "MOTOR6_HB") (pin "35") (pinfunction "OUT1_35") (pintype "bidirectional"))
      (node (ref "MOTOR6_HB") (pin "36") (pinfunction "OUT1_36") (pintype "bidirectional"))
      (node (ref "MOTOR6_HB") (pin "4") (pinfunction "OUT1_4") (pintype "bidirectional"))
    )
    (net (code "66") (name "MOTOR6_2") (class "Default")
      (node (ref "MOTOR6") (pin "C1") (pinfunction "P$1_C1") (pintype "bidirectional"))
      (node (ref "MOTOR6_HB") (pin "15") (pinfunction "OUT2_15") (pintype "bidirectional"))
      (node (ref "MOTOR6_HB") (pin "16") (pinfunction "OUT2_16") (pintype "bidirectional"))
      (node (ref "MOTOR6_HB") (pin "17") (pinfunction "OUT2_17") (pintype "bidirectional"))
      (node (ref "MOTOR6_HB") (pin "18") (pinfunction "OUT2_18") (pintype "bidirectional"))
      (node (ref "MOTOR6_HB") (pin "19") (pinfunction "OUT2_19") (pintype "bidirectional"))
      (node (ref "MOTOR6_HB") (pin "20") (pinfunction "OUT2_20") (pintype "bidirectional"))
      (node (ref "MOTOR6_HB") (pin "21") (pinfunction "OUT2_21") (pintype "bidirectional"))
      (node (ref "MOTOR6_HB") (pin "22") (pinfunction "OUT2_22") (pintype "bidirectional"))
    )
    (net (code "67") (name "MOTOR6_CURRENT_SENSOR") (class "Default")
      (node (ref "C38") (pin "1") (pinfunction "1_1") (pintype "passive"))
      (node (ref "U1") (pin "P$2") (pinfunction "PD1_P$2") (pintype "bidirectional"))
      (node (ref "U7") (pin "7") (pinfunction "VIOUT_7") (pintype "bidirectional"))
    )
    (net (code "68") (name "MOTOR6_ENABLE") (class "Default")
      (node (ref "MOTOR6_HB") (pin "27") (pinfunction "INH_27") (pintype "bidirectional"))
      (node (ref "U1") (pin "P$118") (pinfunction "PP0_P$118") (pintype "bidirectional"))
    )
    (net (code "69") (name "MOTOR6_POWER") (class "Default")
      (node (ref "C76") (pin "2") (pinfunction "2_2") (pintype "passive"))
      (node (ref "C77") (pin "2") (pinfunction "2_2") (pintype "passive"))
      (node (ref "MOTOR6_HB") (pin "11") (pinfunction "VS_11") (pintype "bidirectional"))
      (node (ref "MOTOR6_HB") (pin "12") (pinfunction "VS_12") (pintype "bidirectional"))
      (node (ref "MOTOR6_HB") (pin "13") (pinfunction "VS_13") (pintype "bidirectional"))
      (node (ref "MOTOR6_HB") (pin "14") (pinfunction "VS_14") (pintype "bidirectional"))
      (node (ref "MOTOR6_HB") (pin "29") (pinfunction "VS_29") (pintype "bidirectional"))
      (node (ref "MOTOR6_HB") (pin "30") (pinfunction "VS_30") (pintype "bidirectional"))
      (node (ref "MOTOR6_HB") (pin "31") (pinfunction "VS_31") (pintype "bidirectional"))
      (node (ref "MOTOR6_HB") (pin "32") (pinfunction "VS_32") (pintype "bidirectional"))
      (node (ref "U7") (pin "3") (pinfunction "IP-_3") (pintype "bidirectional"))
      (node (ref "U7") (pin "4") (pinfunction "IP-_4") (pintype "bidirectional"))
    )
    (net (code "70") (name "MOTOR6_PWM1") (class "Default")
      (node (ref "MOTOR6_HB") (pin "9") (pinfunction "IN1_9") (pintype "bidirectional"))
      (node (ref "PWM_DRIVER") (pin "17") (pinfunction "PWM10_17") (pintype "output"))
    )
    (net (code "71") (name "MOTOR6_PWM2") (class "Default")
      (node (ref "MOTOR6_HB") (pin "10") (pinfunction "IN2_10") (pintype "bidirectional"))
      (node (ref "PWM_DRIVER") (pin "18") (pinfunction "PWM11_18") (pintype "output"))
    )
    (net (code "72") (name "MOTOR7_1") (class "Default")
      (node (ref "MOTOR7") (pin "C2") (pinfunction "P$1_C2") (pintype "bidirectional"))
      (node (ref "MOTOR7_HB") (pin "1") (pinfunction "OUT1_1") (pintype "bidirectional"))
      (node (ref "MOTOR7_HB") (pin "2") (pinfunction "OUT1_2") (pintype "bidirectional"))
      (node (ref "MOTOR7_HB") (pin "3") (pinfunction "OUT1_3") (pintype "bidirectional"))
      (node (ref "MOTOR7_HB") (pin "33") (pinfunction "OUT1_33") (pintype "bidirectional"))
      (node (ref "MOTOR7_HB") (pin "34") (pinfunction "OUT1_34") (pintype "bidirectional"))
      (node (ref "MOTOR7_HB") (pin "35") (pinfunction "OUT1_35") (pintype "bidirectional"))
      (node (ref "MOTOR7_HB") (pin "36") (pinfunction "OUT1_36") (pintype "bidirectional"))
      (node (ref "MOTOR7_HB") (pin "4") (pinfunction "OUT1_4") (pintype "bidirectional"))
    )
    (net (code "73") (name "MOTOR7_2") (class "Default")
      (node (ref "MOTOR7") (pin "C1") (pinfunction "P$1_C1") (pintype "bidirectional"))
      (node (ref "MOTOR7_HB") (pin "15") (pinfunction "OUT2_15") (pintype "bidirectional"))
      (node (ref "MOTOR7_HB") (pin "16") (pinfunction "OUT2_16") (pintype "bidirectional"))
      (node (ref "MOTOR7_HB") (pin "17") (pinfunction "OUT2_17") (pintype "bidirectional"))
      (node (ref "MOTOR7_HB") (pin "18") (pinfunction "OUT2_18") (pintype "bidirectional"))
      (node (ref "MOTOR7_HB") (pin "19") (pinfunction "OUT2_19") (pintype "bidirectional"))
      (node (ref "MOTOR7_HB") (pin "20") (pinfunction "OUT2_20") (pintype "bidirectional"))
      (node (ref "MOTOR7_HB") (pin "21") (pinfunction "OUT2_21") (pintype "bidirectional"))
      (node (ref "MOTOR7_HB") (pin "22") (pinfunction "OUT2_22") (pintype "bidirectional"))
    )
    (net (code "74") (name "MOTOR7_ENABLE") (class "Default")
      (node (ref "MOTOR7_HB") (pin "27") (pinfunction "INH_27") (pintype "bidirectional"))
      (node (ref "U1") (pin "P$119") (pinfunction "PP1_P$119") (pintype "bidirectional"))
    )
    (net (code "75") (name "MOTOR7_PWM1") (class "Default")
      (node (ref "MOTOR7_HB") (pin "9") (pinfunction "IN1_9") (pintype "bidirectional"))
      (node (ref "PWM_DRIVER") (pin "19") (pinfunction "PWM12_19") (pintype "output"))
    )
    (net (code "76") (name "MOTOR7_PWM2") (class "Default")
      (node (ref "MOTOR7_HB") (pin "10") (pinfunction "IN2_10") (pintype "bidirectional"))
      (node (ref "PWM_DRIVER") (pin "20") (pinfunction "PWM13_20") (pintype "output"))
    )
    (net (code "77") (name "MOTOR8_1") (class "Default")
      (node (ref "MOTOR8") (pin "C2") (pinfunction "P$1_C2") (pintype "bidirectional"))
      (node (ref "MOTOR8_HB") (pin "1") (pinfunction "OUT1_1") (pintype "bidirectional"))
      (node (ref "MOTOR8_HB") (pin "2") (pinfunction "OUT1_2") (pintype "bidirectional"))
      (node (ref "MOTOR8_HB") (pin "3") (pinfunction "OUT1_3") (pintype "bidirectional"))
      (node (ref "MOTOR8_HB") (pin "33") (pinfunction "OUT1_33") (pintype "bidirectional"))
      (node (ref "MOTOR8_HB") (pin "34") (pinfunction "OUT1_34") (pintype "bidirectional"))
      (node (ref "MOTOR8_HB") (pin "35") (pinfunction "OUT1_35") (pintype "bidirectional"))
      (node (ref "MOTOR8_HB") (pin "36") (pinfunction "OUT1_36") (pintype "bidirectional"))
      (node (ref "MOTOR8_HB") (pin "4") (pinfunction "OUT1_4") (pintype "bidirectional"))
    )
    (net (code "78") (name "MOTOR8_2") (class "Default")
      (node (ref "MOTOR8") (pin "C1") (pinfunction "P$1_C1") (pintype "bidirectional"))
      (node (ref "MOTOR8_HB") (pin "15") (pinfunction "OUT2_15") (pintype "bidirectional"))
      (node (ref "MOTOR8_HB") (pin "16") (pinfunction "OUT2_16") (pintype "bidirectional"))
      (node (ref "MOTOR8_HB") (pin "17") (pinfunction "OUT2_17") (pintype "bidirectional"))
      (node (ref "MOTOR8_HB") (pin "18") (pinfunction "OUT2_18") (pintype "bidirectional"))
      (node (ref "MOTOR8_HB") (pin "19") (pinfunction "OUT2_19") (pintype "bidirectional"))
      (node (ref "MOTOR8_HB") (pin "20") (pinfunction "OUT2_20") (pintype "bidirectional"))
      (node (ref "MOTOR8_HB") (pin "21") (pinfunction "OUT2_21") (pintype "bidirectional"))
      (node (ref "MOTOR8_HB") (pin "22") (pinfunction "OUT2_22") (pintype "bidirectional"))
    )
    (net (code "79") (name "MOTOR8_ENABLE") (class "Default")
      (node (ref "MOTOR8_HB") (pin "27") (pinfunction "INH_27") (pintype "bidirectional"))
      (node (ref "U1") (pin "P$120") (pinfunction "PB5_P$120") (pintype "bidirectional"))
    )
    (net (code "80") (name "MOTOR8_PWM1") (class "Default")
      (node (ref "MOTOR8_HB") (pin "9") (pinfunction "IN1_9") (pintype "bidirectional"))
      (node (ref "PWM_DRIVER") (pin "21") (pinfunction "PWM14_21") (pintype "output"))
    )
    (net (code "81") (name "MOTOR8_PWM2") (class "Default")
      (node (ref "MOTOR8_HB") (pin "10") (pinfunction "IN2_10") (pintype "bidirectional"))
      (node (ref "PWM_DRIVER") (pin "22") (pinfunction "PWM15_22") (pintype "output"))
    )
    (net (code "82") (name "Net-(3.3V-PadC)") (class "Default")
      (node (ref "3.3V") (pin "C") (pinfunction "C_C") (pintype "passive"))
      (node (ref "R19") (pin "1") (pinfunction "1_1") (pintype "passive"))
    )
    (net (code "83") (name "Net-(3.3V_DCDC_OKI-GND)") (class "Default")
      (node (ref "3.3V_DCDC_OKI") (pin "2") (pinfunction "GND_2") (pintype "bidirectional"))
      (node (ref "C50") (pin "1") (pinfunction "1_1") (pintype "passive"))
    )
    (net (code "84") (name "Net-(3.3V_DCDC_OKI-VIN)") (class "Default")
      (node (ref "12V_LOGIC_IN") (pin "P$1") (pinfunction "P$1_P$1") (pintype "bidirectional"))
      (node (ref "3.3V_DCDC_OKI") (pin "1") (pinfunction "VIN_1") (pintype "bidirectional"))
    )
    (net (code "85") (name "Net-(C5-Pad1)") (class "Default")
      (node (ref "C5") (pin "1") (pinfunction "1_1") (pintype "passive"))
      (node (ref "R5") (pin "1") (pinfunction "1_1") (pintype "passive"))
      (node (ref "R6") (pin "1") (pinfunction "1_1") (pintype "passive"))
      (node (ref "R7") (pin "1") (pinfunction "1_1") (pintype "passive"))
      (node (ref "R8") (pin "1") (pinfunction "1_1") (pintype "passive"))
    )
    (net (code "86") (name "Net-(C5-Pad2)") (class "Default")
      (node (ref "C5") (pin "2") (pinfunction "2_2") (pintype "passive"))
      (node (ref "C6") (pin "1") (pinfunction "1_1") (pintype "passive"))
      (node (ref "R9") (pin "2") (pinfunction "2_2") (pintype "passive"))
    )
    (net (code "87") (name "Net-(C12-Pad1)") (class "Default")
      (node (ref "C12") (pin "1") (pinfunction "1_1") (pintype "passive"))
      (node (ref "C13") (pin "1") (pinfunction "1_1") (pintype "passive"))
      (node (ref "C14") (pin "1") (pinfunction "1_1") (pintype "passive"))
      (node (ref "U1") (pin "P$115") (pinfunction "VDDC_P$115") (pintype "bidirectional"))
      (node (ref "U1") (pin "P$87") (pinfunction "VDDC_P$87") (pintype "bidirectional"))
    )
    (net (code "88") (name "Net-(D1-PadC)") (class "Default")
      (node (ref "D1") (pin "C") (pinfunction "C_C") (pintype "passive"))
      (node (ref "R63") (pin "2") (pinfunction "2_2") (pintype "passive"))
    )
    (net (code "89") (name "Net-(D2-PadC)") (class "Default")
      (node (ref "D2") (pin "C") (pinfunction "C_C") (pintype "passive"))
      (node (ref "R62") (pin "2") (pinfunction "2_2") (pintype "passive"))
    )
    (net (code "90") (name "Net-(D3-PadC)") (class "Default")
      (node (ref "D3") (pin "C") (pinfunction "C_C") (pintype "passive"))
      (node (ref "R61") (pin "2") (pinfunction "2_2") (pintype "passive"))
    )
    (net (code "91") (name "Net-(D4-PadC)") (class "Default")
      (node (ref "D4") (pin "C") (pinfunction "C_C") (pintype "passive"))
      (node (ref "R64") (pin "2") (pinfunction "2_2") (pintype "passive"))
    )
    (net (code "92") (name "Net-(D5-PadC)") (class "Default")
      (node (ref "D5") (pin "C") (pinfunction "C_C") (pintype "passive"))
      (node (ref "R65") (pin "2") (pinfunction "2_2") (pintype "passive"))
    )
    (net (code "93") (name "Net-(D6-PadC)") (class "Default")
      (node (ref "D6") (pin "C") (pinfunction "C_C") (pintype "passive"))
      (node (ref "R66") (pin "2") (pinfunction "2_2") (pintype "passive"))
    )
    (net (code "94") (name "Net-(J1-1)") (class "Default")
      (node (ref "J1") (pin "P$8") (pinfunction "1_P$8") (pintype "bidirectional"))
      (node (ref "U2") (pin "P$16") (pinfunction "P$16_P$16") (pintype "bidirectional"))
      (node (ref "U3") (pin "1") (pinfunction "P$1_1") (pintype "bidirectional"))
      (node (ref "U3") (pin "8") (pinfunction "P$8_8") (pintype "bidirectional"))
    )
    (net (code "95") (name "Net-(J1-2)") (class "Default")
      (node (ref "J1") (pin "P$7") (pinfunction "2_P$7") (pintype "bidirectional"))
      (node (ref "U2") (pin "P$14") (pinfunction "P$14_P$14") (pintype "bidirectional"))
      (node (ref "U3") (pin "2") (pinfunction "P$2_2") (pintype "bidirectional"))
      (node (ref "U3") (pin "7") (pinfunction "P$7_7") (pintype "bidirectional"))
    )
    (net (code "96") (name "Net-(J1-3)") (class "Default")
      (node (ref "J1") (pin "P$6") (pinfunction "3_P$6") (pintype "bidirectional"))
      (node (ref "U2") (pin "P$11") (pinfunction "P$11_P$11") (pintype "bidirectional"))
      (node (ref "U3") (pin "3") (pinfunction "P$3_3") (pintype "bidirectional"))
      (node (ref "U3") (pin "6") (pinfunction "P$6_6") (pintype "bidirectional"))
    )
    (net (code "97") (name "Net-(J1-4)") (class "Default")
      (node (ref "J1") (pin "P$4") (pinfunction "5_P$4") (pintype "bidirectional"))
      (node (ref "J1") (pin "P$5") (pinfunction "4_P$5") (pintype "bidirectional"))
      (node (ref "R7") (pin "2") (pinfunction "2_2") (pintype "passive"))
    )
    (net (code "98") (name "Net-(J1-6)") (class "Default")
      (node (ref "J1") (pin "P$3") (pinfunction "6_P$3") (pintype "bidirectional"))
      (node (ref "U2") (pin "P$9") (pinfunction "P$9_P$9") (pintype "bidirectional"))
      (node (ref "U3") (pin "4") (pinfunction "P$4_4") (pintype "bidirectional"))
      (node (ref "U3") (pin "5") (pinfunction "P$5_5") (pintype "bidirectional"))
    )
    (net (code "99") (name "Net-(J1-7)") (class "Default")
      (node (ref "J1") (pin "P$1") (pinfunction "8_P$1") (pintype "bidirectional"))
      (node (ref "J1") (pin "P$2") (pinfunction "7_P$2") (pintype "bidirectional"))
      (node (ref "R8") (pin "2") (pinfunction "2_2") (pintype "passive"))
    )
    (net (code "100") (name "Net-(LED1-PadC)") (class "Default")
      (node (ref "LED1") (pin "C") (pinfunction "C_C") (pintype "passive"))
      (node (ref "R10") (pin "1") (pinfunction "1_1") (pintype "passive"))
    )
    (net (code "101") (name "Net-(LED2-PadC)") (class "Default")
      (node (ref "LED2") (pin "C") (pinfunction "C_C") (pintype "passive"))
      (node (ref "R11") (pin "1") (pinfunction "1_1") (pintype "passive"))
    )
    (net (code "102") (name "Net-(MAINLINE_CURRENT-IP-)") (class "Default")
      (node (ref "C53") (pin "2") (pinfunction "2_2") (pintype "passive"))
      (node (ref "MAINLINE_CURRENT") (pin "6") (pinfunction "IP-_6") (pintype "bidirectional"))
      (node (ref "Q1") (pin "TAB") (pinfunction "D_TAB") (pintype "bidirectional"))
      (node (ref "TRANSISTOR_DRIVER") (pin "6") (pinfunction "SENSE_6") (pintype "bidirectional"))
      (node (ref "TRANSISTOR_DRIVER") (pin "8") (pinfunction "V+_8") (pintype "bidirectional"))
    )
    (net (code "103") (name "Net-(MAINLINE_CURRENT-VOUT)") (class "Default")
      (node (ref "MAINLINE_CURRENT") (pin "3") (pinfunction "VOUT_3") (pintype "bidirectional"))
      (node (ref "R59") (pin "2") (pinfunction "2_2") (pintype "passive"))
    )
    (net (code "104") (name "Net-(MOTOR1_HB-IS)") (class "Default")
      (node (ref "MOTOR1_HB") (pin "28") (pinfunction "IS_28") (pintype "bidirectional"))
      (node (ref "R20") (pin "2") (pinfunction "2_2") (pintype "passive"))
    )
    (net (code "105") (name "Net-(MOTOR2_HB-IS)") (class "Default")
      (node (ref "MOTOR2_HB") (pin "28") (pinfunction "IS_28") (pintype "bidirectional"))
      (node (ref "R69") (pin "2") (pinfunction "2_2") (pintype "passive"))
    )
    (net (code "106") (name "Net-(MOTOR3_HB-IS)") (class "Default")
      (node (ref "MOTOR3_HB") (pin "28") (pinfunction "IS_28") (pintype "bidirectional"))
      (node (ref "R67") (pin "2") (pinfunction "2_2") (pintype "passive"))
    )
    (net (code "107") (name "Net-(MOTOR4_HB-IS)") (class "Default")
      (node (ref "MOTOR4_HB") (pin "28") (pinfunction "IS_28") (pintype "bidirectional"))
      (node (ref "R18") (pin "2") (pinfunction "2_2") (pintype "passive"))
    )
    (net (code "108") (name "Net-(MOTOR5_HB-IS)") (class "Default")
      (node (ref "MOTOR5_HB") (pin "28") (pinfunction "IS_28") (pintype "bidirectional"))
      (node (ref "R68") (pin "2") (pinfunction "2_2") (pintype "passive"))
    )
    (net (code "109") (name "Net-(MOTOR6_HB-IS)") (class "Default")
      (node (ref "MOTOR6_HB") (pin "28") (pinfunction "IS_28") (pintype "bidirectional"))
      (node (ref "R60") (pin "2") (pinfunction "2_2") (pintype "passive"))
    )
    (net (code "110") (name "Net-(MOTOR7_HB-IS)") (class "Default")
      (node (ref "MOTOR7_HB") (pin "28") (pinfunction "IS_28") (pintype "bidirectional"))
      (node (ref "R49") (pin "2") (pinfunction "2_2") (pintype "passive"))
    )
    (net (code "111") (name "Net-(MOTOR8_HB-IS)") (class "Default")
      (node (ref "MOTOR8_HB") (pin "28") (pinfunction "IS_28") (pintype "bidirectional"))
      (node (ref "R50") (pin "2") (pinfunction "2_2") (pintype "passive"))
    )
    (net (code "112") (name "Net-(Q1-G)") (class "Default")
      (node (ref "Q1") (pin "1") (pinfunction "G_1") (pintype "bidirectional"))
      (node (ref "TRANSISTOR_DRIVER") (pin "5") (pinfunction "GATE_5") (pintype "bidirectional"))
    )
    (net (code "113") (name "Net-(R5-Pad2)") (class "Default")
      (node (ref "R5") (pin "2") (pinfunction "2_2") (pintype "passive"))
      (node (ref "U2") (pin "P$15") (pinfunction "P$15_P$15") (pintype "bidirectional"))
    )
    (net (code "114") (name "Net-(R6-Pad2)") (class "Default")
      (node (ref "R6") (pin "2") (pinfunction "2_2") (pintype "passive"))
      (node (ref "U2") (pin "P$10") (pinfunction "P$10_P$10") (pintype "bidirectional"))
    )
    (net (code "115") (name "Net-(TRANSISTOR_DRIVER-TIMER)") (class "Default")
      (node (ref "C52") (pin "1") (pinfunction "1_1") (pintype "passive"))
      (node (ref "TRANSISTOR_DRIVER") (pin "2") (pinfunction "TIMER_2") (pintype "bidirectional"))
    )
    (net (code "116") (name "Net-(U1B-OSC0)") (class "Default")
      (node (ref "C16") (pin "1") (pinfunction "1_1") (pintype "passive"))
      (node (ref "U1") (pin "P$88") (pinfunction "OSC0_P$88") (pintype "bidirectional"))
      (node (ref "Y1") (pin "P$3") (pinfunction "OSC1_P$3") (pintype "bidirectional"))
    )
    (net (code "117") (name "Net-(U1B-OSC1)") (class "Default")
      (node (ref "R15") (pin "2") (pinfunction "2_2") (pintype "passive"))
      (node (ref "U1") (pin "P$89") (pinfunction "OSC1_P$89") (pintype "bidirectional"))
    )
    (net (code "118") (name "Net-(U1B-RBIAS)") (class "Default")
      (node (ref "R14") (pin "2") (pinfunction "2_2") (pintype "passive"))
      (node (ref "U1") (pin "P$59") (pinfunction "RBIAS_P$59") (pintype "bidirectional"))
    )
    (net (code "119") (name "Net-(U1B-VBAT)") (class "Default")
      (node (ref "C7") (pin "1") (pinfunction "1_1") (pintype "passive"))
      (node (ref "R13") (pin "1") (pinfunction "1_1") (pintype "passive"))
      (node (ref "U1") (pin "P$68") (pinfunction "VBAT_P$68") (pintype "bidirectional"))
    )
    (net (code "120") (name "Net-(U1B-XOSC0)") (class "Default")
      (node (ref "C19") (pin "1") (pinfunction "1_1") (pintype "passive"))
      (node (ref "U1") (pin "P$66") (pinfunction "XOSC0_P$66") (pintype "bidirectional"))
      (node (ref "Y2") (pin "P$1") (pinfunction "P$1_P$1") (pintype "bidirectional"))
    )
    (net (code "121") (name "Net-(U1B-XOSC1)") (class "Default")
      (node (ref "C18") (pin "1") (pinfunction "1_1") (pintype "passive"))
      (node (ref "U1") (pin "P$67") (pinfunction "XOSC1_P$67") (pintype "bidirectional"))
      (node (ref "Y2") (pin "P$2") (pinfunction "P$2_P$2") (pintype "bidirectional"))
    )
    (net (code "122") (name "Net-(U1B-~{RESET})") (class "Default")
      (node (ref "C17") (pin "1") (pinfunction "1_1") (pintype "passive"))
      (node (ref "R16") (pin "1") (pinfunction "1_1") (pintype "passive"))
      (node (ref "R17") (pin "2") (pinfunction "2_2") (pintype "passive"))
      (node (ref "U1") (pin "P$70") (pinfunction "~{RESET}_P$70") (pintype "bidirectional"))
    )
    (net (code "123") (name "Net-(U1B-~{WAKE})") (class "Default")
      (node (ref "R12") (pin "1") (pinfunction "1_1") (pintype "passive"))
      (node (ref "U1") (pin "P$64") (pinfunction "~{WAKE}_P$64") (pintype "bidirectional"))
    )
    (net (code "124") (name "Net-(U4-FILTER)") (class "Default")
      (node (ref "C28") (pin "1") (pinfunction "1_1") (pintype "passive"))
      (node (ref "U4") (pin "6") (pinfunction "FILTER_6") (pintype "bidirectional"))
    )
    (net (code "125") (name "Net-(U5-FILTER)") (class "Default")
      (node (ref "C31") (pin "1") (pinfunction "1_1") (pintype "passive"))
      (node (ref "U5") (pin "6") (pinfunction "FILTER_6") (pintype "bidirectional"))
    )
    (net (code "126") (name "Net-(U6-FILTER)") (class "Default")
      (node (ref "C34") (pin "1") (pinfunction "1_1") (pintype "passive"))
      (node (ref "U6") (pin "6") (pinfunction "FILTER_6") (pintype "bidirectional"))
    )
    (net (code "127") (name "Net-(U7-FILTER)") (class "Default")
      (node (ref "C37") (pin "1") (pinfunction "1_1") (pintype "passive"))
      (node (ref "U7") (pin "6") (pinfunction "FILTER_6") (pintype "bidirectional"))
    )
    (net (code "128") (name "Net-(U8-FILTER)") (class "Default")
      (node (ref "C25") (pin "1") (pinfunction "1_1") (pintype "passive"))
      (node (ref "U8") (pin "6") (pinfunction "FILTER_6") (pintype "bidirectional"))
    )
    (net (code "129") (name "Net-(U9-FILTER)") (class "Default")
      (node (ref "C40") (pin "1") (pinfunction "1_1") (pintype "passive"))
      (node (ref "U9") (pin "6") (pinfunction "FILTER_6") (pintype "bidirectional"))
    )
    (net (code "130") (name "Net-(Y1-OSC0)") (class "Default")
      (node (ref "C15") (pin "1") (pinfunction "1_1") (pintype "passive"))
      (node (ref "R15") (pin "1") (pinfunction "1_1") (pintype "passive"))
      (node (ref "Y1") (pin "P$1") (pinfunction "OSC0_P$1") (pintype "bidirectional"))
    )
    (net (code "131") (name "PWM_ADDRESS_BIT_A0") (class "Default")
      (node (ref "U1") (pin "P$12") (pinfunction "PE3_P$12") (pintype "bidirectional"))
    )
    (net (code "132") (name "PWM_ADDRESS_BIT_A1") (class "Default")
      (node (ref "U1") (pin "P$11") (pinfunction "PQ2_P$11") (pintype "bidirectional"))
    )
    (net (code "133") (name "PWM_ADDRESS_BIT_A2") (class "Default")
      (node (ref "U1") (pin "P$6") (pinfunction "PQ1_P$6") (pintype "bidirectional"))
    )
    (net (code "134") (name "PWM_ADDRESS_BIT_A3") (class "Default")
      (node (ref "U1") (pin "P$5") (pinfunction "PQ0_P$5") (pintype "bidirectional"))
    )
    (net (code "135") (name "PWM_ADDRESS_BIT_A4") (class "Default")
      (node (ref "U1") (pin "P$4") (pinfunction "PD3_P$4") (pintype "bidirectional"))
    )
    (net (code "136") (name "PWM_ADDRESS_BIT_A5") (class "Default")
      (node (ref "U1") (pin "P$13") (pinfunction "PE2_P$13") (pintype "bidirectional"))
    )
    (net (code "137") (name "PWM_DRIVER_SCL") (class "Default")
      (node (ref "PWM_DRIVER") (pin "26") (pinfunction "SCL_26") (pintype "bidirectional"))
      (node (ref "SCL_PULLUP") (pin "2") (pinfunction "2_2") (pintype "passive"))
      (node (ref "U1") (pin "P$112") (pinfunction "PN5_P$112") (pintype "bidirectional"))
    )
    (net (code "138") (name "PWM_DRIVER_SDA") (class "Default")
      (node (ref "PWM_DRIVER") (pin "27") (pinfunction "SDA_27") (pintype "bidirectional"))
      (node (ref "SDA_PULLUP") (pin "2") (pinfunction "2_2") (pintype "passive"))
      (node (ref "U1") (pin "P$111") (pinfunction "PN4_P$111") (pintype "bidirectional"))
    )
    (net (code "139") (name "PWM_OUTPUT_ENABLE") (class "Default")
      (node (ref "OE_PULLUP") (pin "2") (pinfunction "2_2") (pintype "passive"))
      (node (ref "PWM_DRIVER") (pin "23") (pinfunction "#OE_23") (pintype "input"))
      (node (ref "U1") (pin "P$14") (pinfunction "PE1_P$14") (pintype "bidirectional"))
    )
    (net (code "140") (name "RX") (class "Default")
      (node (ref "J2") (pin "P7") (pinfunction "P$7_P7") (pintype "bidirectional"))
      (node (ref "U1") (pin "P$33") (pinfunction "PA0_P$33") (pintype "bidirectional"))
    )
    (net (code "141") (name "SWITCH") (class "Default")
      (node (ref "R57") (pin "1") (pinfunction "1_1") (pintype "passive"))
      (node (ref "S5") (pin "P$3") (pinfunction "O_P$3") (pintype "passive"))
      (node (ref "U1") (pin "P$29") (pinfunction "PH0_P$29") (pintype "bidirectional"))
    )
    (net (code "142") (name "TARGET_TCK{slash}SWCLK") (class "Default")
      (node (ref "J2") (pin "P4") (pinfunction "TCK_P4") (pintype "bidirectional"))
      (node (ref "U1") (pin "P$100") (pinfunction "PC0_P$100") (pintype "bidirectional"))
    )
    (net (code "143") (name "TARGET_TDI") (class "Default")
      (node (ref "J2") (pin "P8") (pinfunction "TDI_P8") (pintype "bidirectional"))
      (node (ref "U1") (pin "P$98") (pinfunction "PC2_P$98") (pintype "bidirectional"))
    )
    (net (code "144") (name "TARGET_TDO{slash}SWO") (class "Default")
      (node (ref "J2") (pin "P6") (pinfunction "TDO_P6") (pintype "bidirectional"))
      (node (ref "U1") (pin "P$97") (pinfunction "PC3_P$97") (pintype "bidirectional"))
    )
    (net (code "145") (name "TARGET_TMS{slash}SWDIO") (class "Default")
      (node (ref "J2") (pin "P2") (pinfunction "TMS_P2") (pintype "bidirectional"))
      (node (ref "U1") (pin "P$99") (pinfunction "PC1_P$99") (pintype "bidirectional"))
    )
    (net (code "146") (name "TX") (class "Default")
      (node (ref "J2") (pin "P9") (pinfunction "GND1_P9") (pintype "bidirectional"))
      (node (ref "U1") (pin "P$34") (pinfunction "PA1_P$34") (pintype "bidirectional"))
    )
    (net (code "147") (name "VCC_12V") (class "Default")
      (node (ref "C61") (pin "2") (pinfunction "2_2") (pintype "passive"))
      (node (ref "C62") (pin "2") (pinfunction "2_2") (pintype "passive"))
      (node (ref "MAINLINE_CURRENT") (pin "5") (pinfunction "IP+_5") (pintype "bidirectional"))
      (node (ref "POWER_12V") (pin "P$1") (pinfunction "P$1_P$1") (pintype "bidirectional"))
      (node (ref "POWER_12V2") (pin "P$1") (pinfunction "P$1_P$1") (pintype "bidirectional"))
    )
    (net (code "148") (name "unconnected-(S5-S-PadP$1)") (class "Default")
      (node (ref "S5") (pin "P$1") (pinfunction "S_P$1") (pintype "passive"))
    )
    (net (code "149") (name "unconnected-(TRANSISTOR_DRIVER-FAULT-Pad3)") (class "Default")
      (node (ref "TRANSISTOR_DRIVER") (pin "3") (pinfunction "FAULT_3") (pintype "bidirectional"))
    )
    (net (code "150") (name "unconnected-(U1A-PA2-PadP$35)") (class "Default")
      (node (ref "U1") (pin "P$35") (pinfunction "PA2_P$35") (pintype "bidirectional"))
    )
    (net (code "151") (name "unconnected-(U1A-PA3-PadP$36)") (class "Default")
      (node (ref "U1") (pin "P$36") (pinfunction "PA3_P$36") (pintype "bidirectional"))
    )
    (net (code "152") (name "unconnected-(U1A-PA4-PadP$37)") (class "Default")
      (node (ref "U1") (pin "P$37") (pinfunction "PA4_P$37") (pintype "bidirectional"))
    )
    (net (code "153") (name "unconnected-(U1A-PA5-PadP$38)") (class "Default")
      (node (ref "U1") (pin "P$38") (pinfunction "PA5_P$38") (pintype "bidirectional"))
    )
    (net (code "154") (name "unconnected-(U1A-PA6-PadP$40)") (class "Default")
      (node (ref "U1") (pin "P$40") (pinfunction "PA6_P$40") (pintype "bidirectional"))
    )
    (net (code "155") (name "unconnected-(U1A-PA7-PadP$41)") (class "Default")
      (node (ref "U1") (pin "P$41") (pinfunction "PA7_P$41") (pintype "bidirectional"))
    )
    (net (code "156") (name "unconnected-(U1A-PB0-PadP$95)") (class "Default")
      (node (ref "U1") (pin "P$95") (pinfunction "PB0_P$95") (pintype "bidirectional"))
    )
    (net (code "157") (name "unconnected-(U1A-PB2-PadP$91)") (class "Default")
      (node (ref "U1") (pin "P$91") (pinfunction "PB2_P$91") (pintype "bidirectional"))
    )
    (net (code "158") (name "unconnected-(U1A-PB3-PadP$92)") (class "Default")
      (node (ref "U1") (pin "P$92") (pinfunction "PB3_P$92") (pintype "bidirectional"))
    )
    (net (code "159") (name "unconnected-(U1A-PD7-PadP$128)") (class "Default")
      (node (ref "U1") (pin "P$128") (pinfunction "PD7_P$128") (pintype "bidirectional"))
    )
    (net (code "160") (name "unconnected-(U1A-PF1-PadP$43)") (class "Default")
      (node (ref "U1") (pin "P$43") (pinfunction "PF1_P$43") (pintype "bidirectional"))
    )
    (net (code "161") (name "unconnected-(U1A-PF2-PadP$44)") (class "Default")
      (node (ref "U1") (pin "P$44") (pinfunction "PF2_P$44") (pintype "bidirectional"))
    )
    (net (code "162") (name "unconnected-(U1A-PF3-PadP$45)") (class "Default")
      (node (ref "U1") (pin "P$45") (pinfunction "PF3_P$45") (pintype "bidirectional"))
    )
    (net (code "163") (name "unconnected-(U1A-PG0-PadP$49)") (class "Default")
      (node (ref "U1") (pin "P$49") (pinfunction "PG0_P$49") (pintype "bidirectional"))
    )
    (net (code "164") (name "unconnected-(U1A-PG1-PadP$50)") (class "Default")
      (node (ref "U1") (pin "P$50") (pinfunction "PG1_P$50") (pintype "bidirectional"))
    )
    (net (code "165") (name "unconnected-(U1A-PK4-PadP$63)") (class "Default")
      (node (ref "U1") (pin "P$63") (pinfunction "PK4_P$63") (pintype "bidirectional"))
    )
    (net (code "166") (name "unconnected-(U1A-PK5-PadP$62)") (class "Default")
      (node (ref "U1") (pin "P$62") (pinfunction "PK5_P$62") (pintype "bidirectional"))
    )
    (net (code "167") (name "unconnected-(U1A-PK6-PadP$61)") (class "Default")
      (node (ref "U1") (pin "P$61") (pinfunction "PK6_P$61") (pintype "bidirectional"))
    )
    (net (code "168") (name "unconnected-(U1A-PK7-PadP$60)") (class "Default")
      (node (ref "U1") (pin "P$60") (pinfunction "PK7_P$60") (pintype "bidirectional"))
    )
    (net (code "169") (name "unconnected-(U1A-PL0-PadP$81)") (class "Default")
      (node (ref "U1") (pin "P$81") (pinfunction "PL0_P$81") (pintype "bidirectional"))
    )
    (net (code "170") (name "unconnected-(U1A-PL1-PadP$82)") (class "Default")
      (node (ref "U1") (pin "P$82") (pinfunction "PL1_P$82") (pintype "bidirectional"))
    )
    (net (code "171") (name "unconnected-(U1A-PL2-PadP$83)") (class "Default")
      (node (ref "U1") (pin "P$83") (pinfunction "PL2_P$83") (pintype "bidirectional"))
    )
    (net (code "172") (name "unconnected-(U1A-PL3-PadP$84)") (class "Default")
      (node (ref "U1") (pin "P$84") (pinfunction "PL3_P$84") (pintype "bidirectional"))
    )
    (net (code "173") (name "unconnected-(U1A-PL4-PadP$85)") (class "Default")
      (node (ref "U1") (pin "P$85") (pinfunction "PL4_P$85") (pintype "bidirectional"))
    )
    (net (code "174") (name "unconnected-(U1A-PL5-PadP$86)") (class "Default")
      (node (ref "U1") (pin "P$86") (pinfunction "PL5_P$86") (pintype "bidirectional"))
    )
    (net (code "175") (name "unconnected-(U1A-PL6-PadP$94)") (class "Default")
      (node (ref "U1") (pin "P$94") (pinfunction "PL6_P$94") (pintype "bidirectional"))
    )
    (net (code "176") (name "unconnected-(U1A-PL7-PadP$93)") (class "Default")
      (node (ref "U1") (pin "P$93") (pinfunction "PL7_P$93") (pintype "bidirectional"))
    )
    (net (code "177") (name "unconnected-(U1A-PM1-PadP$77)") (class "Default")
      (node (ref "U1") (pin "P$77") (pinfunction "PM1_P$77") (pintype "bidirectional"))
    )
    (net (code "178") (name "unconnected-(U1A-PM3-PadP$75)") (class "Default")
      (node (ref "U1") (pin "P$75") (pinfunction "PM3_P$75") (pintype "bidirectional"))
    )
    (net (code "179") (name "unconnected-(U1A-PM5-PadP$73)") (class "Default")
      (node (ref "U1") (pin "P$73") (pinfunction "PM5_P$73") (pintype "bidirectional"))
    )
    (net (code "180") (name "unconnected-(U1A-PM7-PadP$71)") (class "Default")
      (node (ref "U1") (pin "P$71") (pinfunction "PM7_P$71") (pintype "bidirectional"))
    )
    (net (code "181") (name "unconnected-(U1A-PN0-PadP$107)") (class "Default")
      (node (ref "U1") (pin "P$107") (pinfunction "PN0_P$107") (pintype "bidirectional"))
    )
    (net (code "182") (name "unconnected-(U1A-PN1-PadP$108)") (class "Default")
      (node (ref "U1") (pin "P$108") (pinfunction "PN1_P$108") (pintype "bidirectional"))
    )
    (net (code "183") (name "unconnected-(U1A-PP2-PadP$103)") (class "Default")
      (node (ref "U1") (pin "P$103") (pinfunction "PP2_P$103") (pintype "bidirectional"))
    )
    (net (code "184") (name "unconnected-(U1A-PP3-PadP$104)") (class "Default")
      (node (ref "U1") (pin "P$104") (pinfunction "PP3_P$104") (pintype "bidirectional"))
    )
    (net (code "185") (name "unconnected-(U1A-PP4-PadP$105)") (class "Default")
      (node (ref "U1") (pin "P$105") (pinfunction "PP4_P$105") (pintype "bidirectional"))
    )
    (net (code "186") (name "unconnected-(U1A-PP5-PadP$106)") (class "Default")
      (node (ref "U1") (pin "P$106") (pinfunction "PP5_P$106") (pintype "bidirectional"))
    )
    (net (code "187") (name "unconnected-(U1A-PQ4-PadP$102)") (class "Default")
      (node (ref "U1") (pin "P$102") (pinfunction "PQ4_P$102") (pintype "bidirectional"))
    )
    (net (code "188") (name "unconnected-(U1B-~{HIB}-PadP$65)") (class "Default")
      (node (ref "U1") (pin "P$65") (pinfunction "~{HIB}_P$65") (pintype "bidirectional"))
    )
    (net (code "189") (name "unconnected-(Y1-NC2-PadP$2)") (class "Default")
      (node (ref "Y1") (pin "P$2") (pinfunction "NC2_P$2") (pintype "bidirectional"))
    )
    (net (code "190") (name "unconnected-(Y1-NC4-PadP$4)") (class "Default")
      (node (ref "Y1") (pin "P$4") (pinfunction "NC4_P$4") (pintype "bidirectional"))
    )
    (net (code "191") (name "~{RESET}") (class "Default")
      (node (ref "J2") (pin "P10") (pinfunction "~{RESET}_P10") (pintype "bidirectional"))
      (node (ref "R16") (pin "2") (pinfunction "2_2") (pintype "passive"))
      (node (ref "S1") (pin "P$3") (pinfunction "1_P$3") (pintype "passive"))
      (node (ref "S1") (pin "P$4") (pinfunction "1_P$4") (pintype "passive"))
    )
  )
)
